# Connectors.net
KiCad netlist of a schematic drawn in Altium Designer
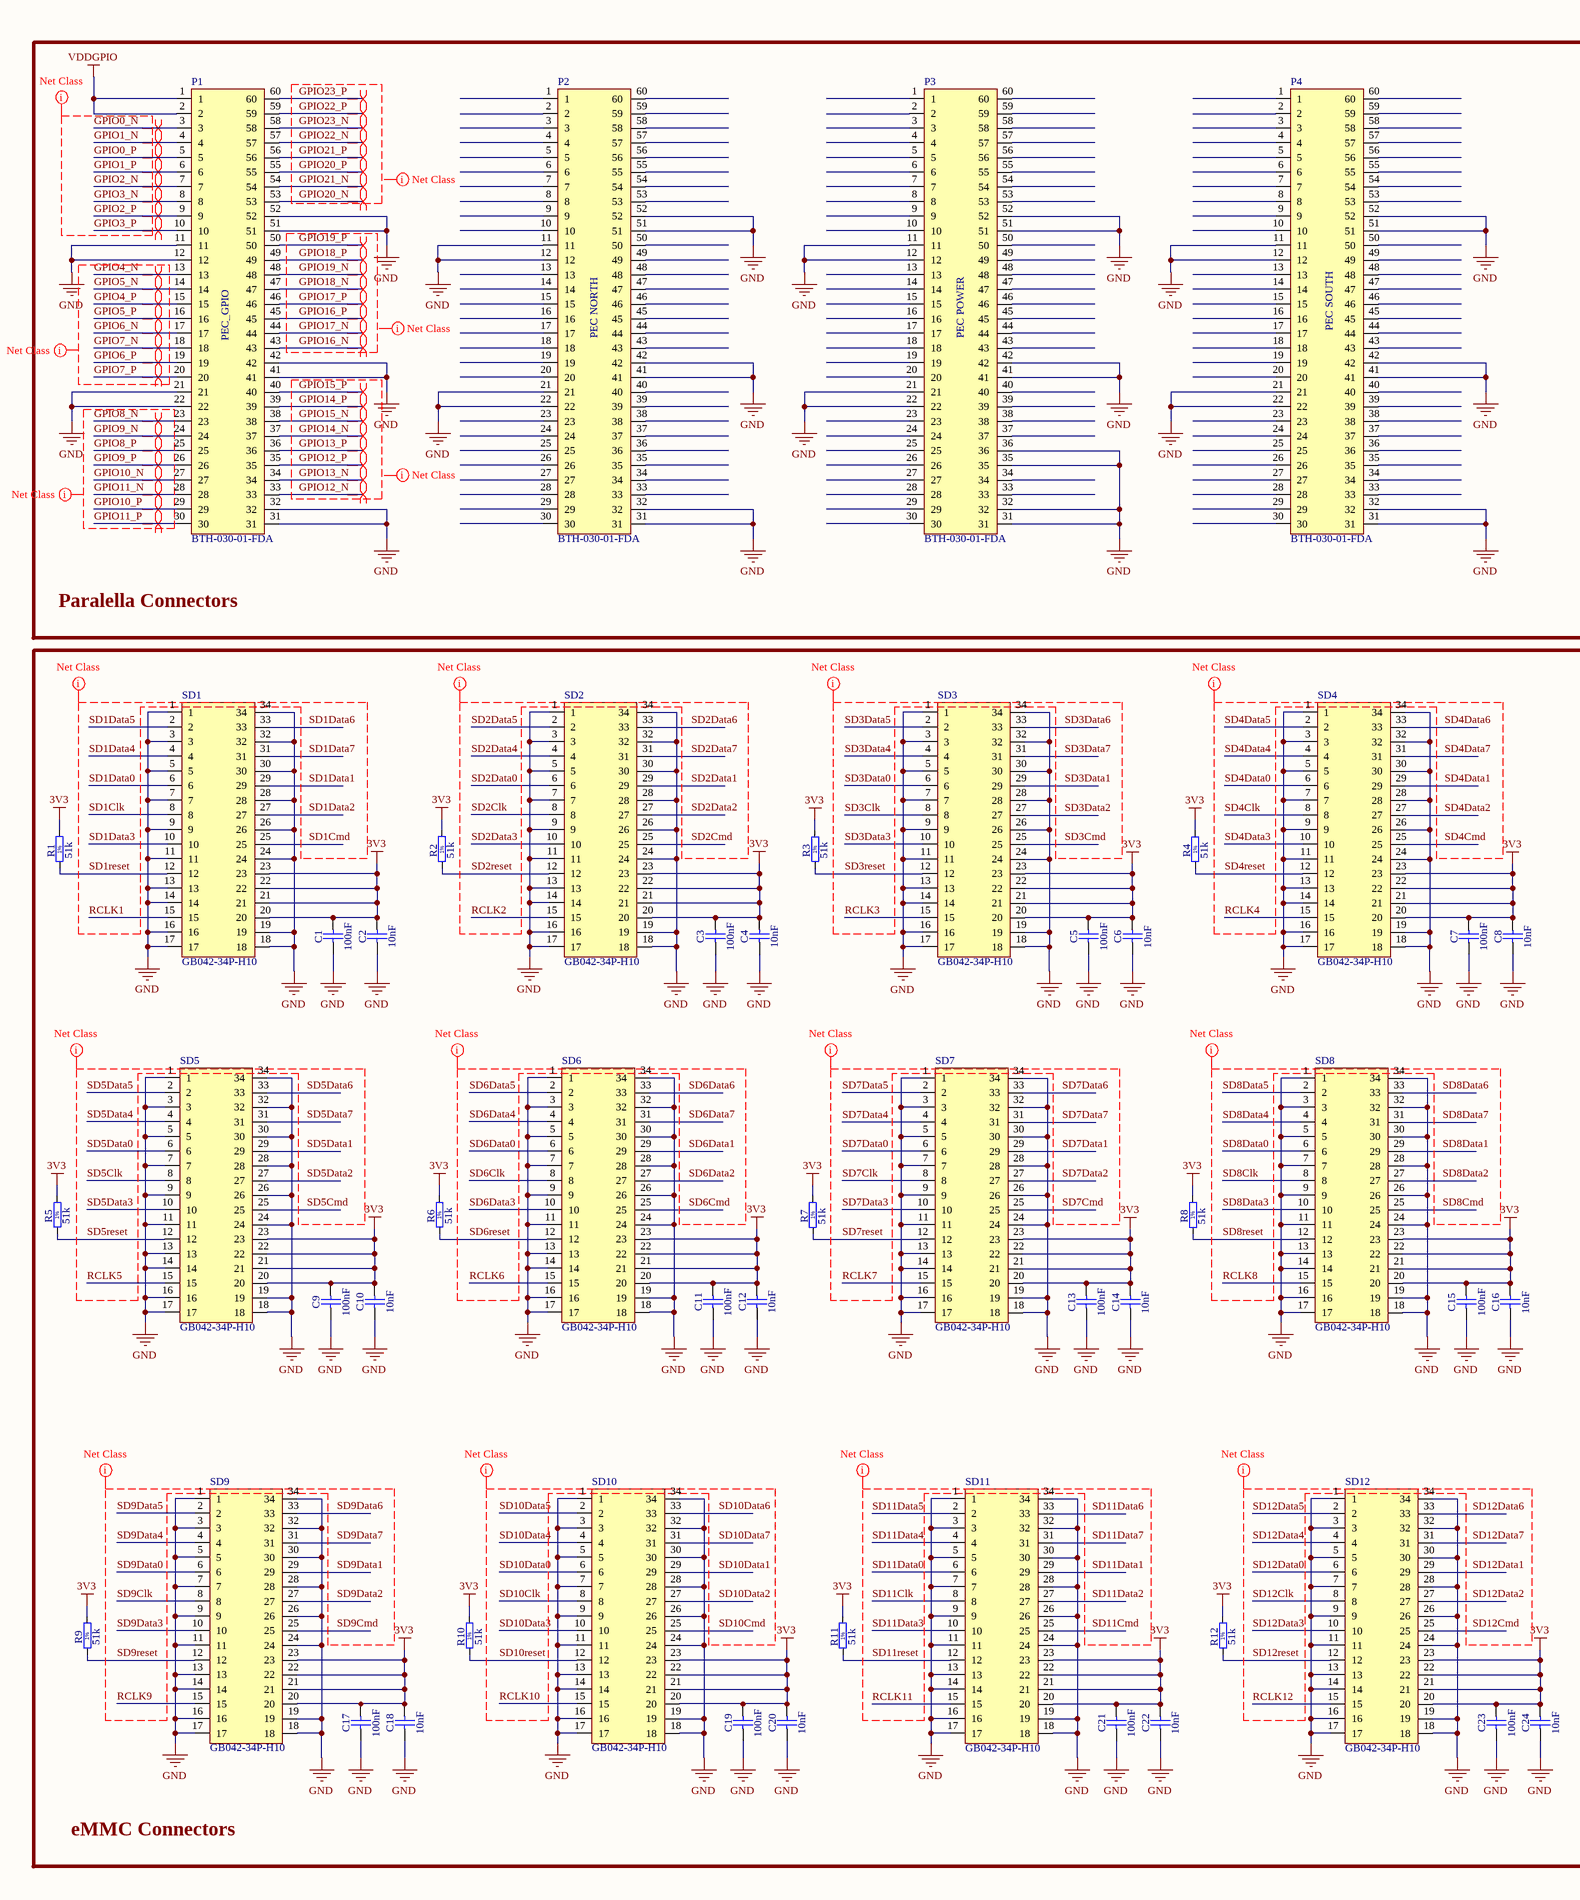
[diagram p0: Connectors.SchDoc, left]
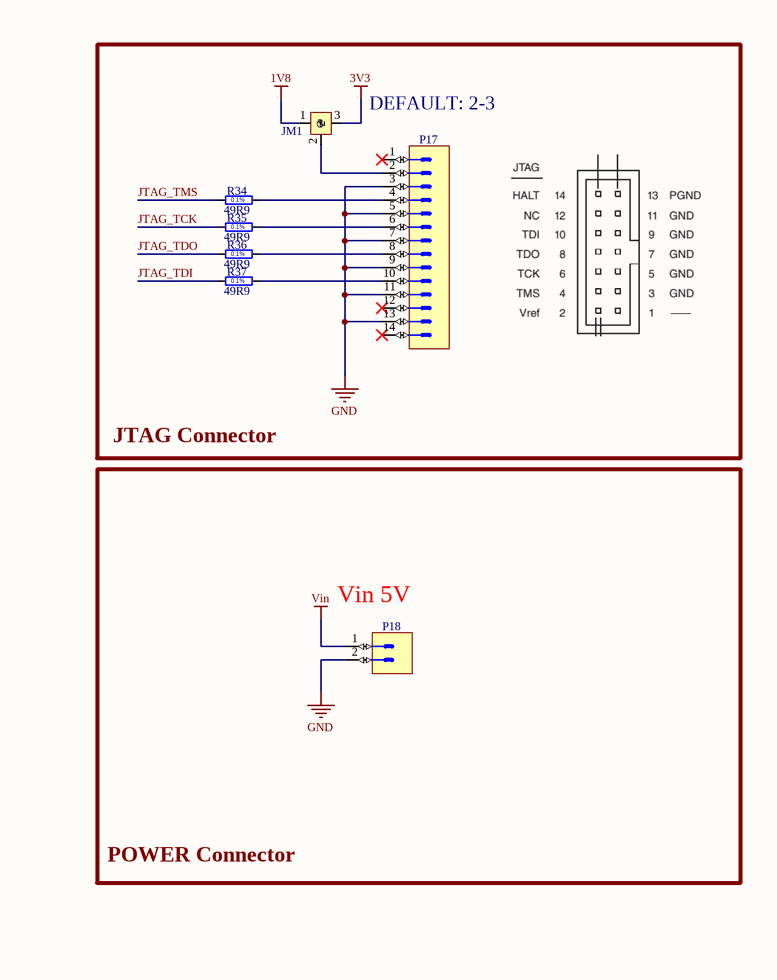
[diagram p1: Connectors.SchDoc, right]

(export (version "E")
  (design (tool "Eeschema 10.0.6"))
  (components
    (comp (ref "C1")
      (value "100nF")
      (footprint "CAPC1608X87N")
      (description "Non-polarised capacitor")
      (fields
        (field (name "PART NUMBER") "CC0603_100NF_50V_10%_X7R")
        (field (name "VOLTAGE") "50V")
        (field (name "AUTHOR") "CERN DEM JLC")
      )
      (libsource (lib "Capacitors") (part "Capacitor - non polarized"))
    )
    (comp (ref "C2")
      (value "10nF")
      (footprint "CAPC1608X87N")
      (description "Non-polarised capacitor")
      (fields
        (field (name "PART NUMBER") "CC0603_10NF_50V_10%_X7R")
        (field (name "VOLTAGE") "50V")
        (field (name "AUTHOR") "CERN DEM JLC")
      )
      (libsource (lib "Capacitors") (part "Capacitor - non polarized"))
    )
    (comp (ref "C3")
      (value "100nF")
      (footprint "CAPC1608X87N")
      (description "Non-polarised capacitor")
      (fields
        (field (name "PART NUMBER") "CC0603_100NF_50V_10%_X7R")
        (field (name "VOLTAGE") "50V")
        (field (name "AUTHOR") "CERN DEM JLC")
      )
      (libsource (lib "Capacitors") (part "Capacitor - non polarized"))
    )
    (comp (ref "C4")
      (value "10nF")
      (footprint "CAPC1608X87N")
      (description "Non-polarised capacitor")
      (fields
        (field (name "PART NUMBER") "CC0603_10NF_50V_10%_X7R")
        (field (name "VOLTAGE") "50V")
        (field (name "AUTHOR") "CERN DEM JLC")
      )
      (libsource (lib "Capacitors") (part "Capacitor - non polarized"))
    )
    (comp (ref "C5")
      (value "100nF")
      (footprint "CAPC1608X87N")
      (description "Non-polarised capacitor")
      (fields
        (field (name "PART NUMBER") "CC0603_100NF_50V_10%_X7R")
        (field (name "VOLTAGE") "50V")
        (field (name "AUTHOR") "CERN DEM JLC")
      )
      (libsource (lib "Capacitors") (part "Capacitor - non polarized"))
    )
    (comp (ref "C6")
      (value "10nF")
      (footprint "CAPC1608X87N")
      (description "Non-polarised capacitor")
      (fields
        (field (name "PART NUMBER") "CC0603_10NF_50V_10%_X7R")
        (field (name "VOLTAGE") "50V")
        (field (name "AUTHOR") "CERN DEM JLC")
      )
      (libsource (lib "Capacitors") (part "Capacitor - non polarized"))
    )
    (comp (ref "C7")
      (value "100nF")
      (footprint "CAPC1608X87N")
      (description "Non-polarised capacitor")
      (fields
        (field (name "PART NUMBER") "CC0603_100NF_50V_10%_X7R")
        (field (name "VOLTAGE") "50V")
        (field (name "AUTHOR") "CERN DEM JLC")
      )
      (libsource (lib "Capacitors") (part "Capacitor - non polarized"))
    )
    (comp (ref "C8")
      (value "10nF")
      (footprint "CAPC1608X87N")
      (description "Non-polarised capacitor")
      (fields
        (field (name "PART NUMBER") "CC0603_10NF_50V_10%_X7R")
        (field (name "VOLTAGE") "50V")
        (field (name "AUTHOR") "CERN DEM JLC")
      )
      (libsource (lib "Capacitors") (part "Capacitor - non polarized"))
    )
    (comp (ref "C9")
      (value "100nF")
      (footprint "CAPC1608X87N")
      (description "Non-polarised capacitor")
      (fields
        (field (name "PART NUMBER") "CC0603_100NF_50V_10%_X7R")
        (field (name "VOLTAGE") "50V")
        (field (name "AUTHOR") "CERN DEM JLC")
      )
      (libsource (lib "Capacitors") (part "Capacitor - non polarized"))
    )
    (comp (ref "C10")
      (value "10nF")
      (footprint "CAPC1608X87N")
      (description "Non-polarised capacitor")
      (fields
        (field (name "PART NUMBER") "CC0603_10NF_50V_10%_X7R")
        (field (name "VOLTAGE") "50V")
        (field (name "AUTHOR") "CERN DEM JLC")
      )
      (libsource (lib "Capacitors") (part "Capacitor - non polarized"))
    )
    (comp (ref "C11")
      (value "100nF")
      (footprint "CAPC1608X87N")
      (description "Non-polarised capacitor")
      (fields
        (field (name "PART NUMBER") "CC0603_100NF_50V_10%_X7R")
        (field (name "VOLTAGE") "50V")
        (field (name "AUTHOR") "CERN DEM JLC")
      )
      (libsource (lib "Capacitors") (part "Capacitor - non polarized"))
    )
    (comp (ref "C12")
      (value "10nF")
      (footprint "CAPC1608X87N")
      (description "Non-polarised capacitor")
      (fields
        (field (name "PART NUMBER") "CC0603_10NF_50V_10%_X7R")
        (field (name "VOLTAGE") "50V")
        (field (name "AUTHOR") "CERN DEM JLC")
      )
      (libsource (lib "Capacitors") (part "Capacitor - non polarized"))
    )
    (comp (ref "C13")
      (value "100nF")
      (footprint "CAPC1608X87N")
      (description "Non-polarised capacitor")
      (fields
        (field (name "PART NUMBER") "CC0603_100NF_50V_10%_X7R")
        (field (name "VOLTAGE") "50V")
        (field (name "AUTHOR") "CERN DEM JLC")
      )
      (libsource (lib "Capacitors") (part "Capacitor - non polarized"))
    )
    (comp (ref "C14")
      (value "10nF")
      (footprint "CAPC1608X87N")
      (description "Non-polarised capacitor")
      (fields
        (field (name "PART NUMBER") "CC0603_10NF_50V_10%_X7R")
        (field (name "VOLTAGE") "50V")
        (field (name "AUTHOR") "CERN DEM JLC")
      )
      (libsource (lib "Capacitors") (part "Capacitor - non polarized"))
    )
    (comp (ref "C15")
      (value "100nF")
      (footprint "CAPC1608X87N")
      (description "Non-polarised capacitor")
      (fields
        (field (name "PART NUMBER") "CC0603_100NF_50V_10%_X7R")
        (field (name "VOLTAGE") "50V")
        (field (name "AUTHOR") "CERN DEM JLC")
      )
      (libsource (lib "Capacitors") (part "Capacitor - non polarized"))
    )
    (comp (ref "C16")
      (value "10nF")
      (footprint "CAPC1608X87N")
      (description "Non-polarised capacitor")
      (fields
        (field (name "PART NUMBER") "CC0603_10NF_50V_10%_X7R")
        (field (name "VOLTAGE") "50V")
        (field (name "AUTHOR") "CERN DEM JLC")
      )
      (libsource (lib "Capacitors") (part "Capacitor - non polarized"))
    )
    (comp (ref "C17")
      (value "100nF")
      (footprint "CAPC1608X87N")
      (description "Non-polarised capacitor")
      (fields
        (field (name "PART NUMBER") "CC0603_100NF_50V_10%_X7R")
        (field (name "VOLTAGE") "50V")
        (field (name "AUTHOR") "CERN DEM JLC")
      )
      (libsource (lib "Capacitors") (part "Capacitor - non polarized"))
    )
    (comp (ref "C18")
      (value "10nF")
      (footprint "CAPC1608X87N")
      (description "Non-polarised capacitor")
      (fields
        (field (name "PART NUMBER") "CC0603_10NF_50V_10%_X7R")
        (field (name "VOLTAGE") "50V")
        (field (name "AUTHOR") "CERN DEM JLC")
      )
      (libsource (lib "Capacitors") (part "Capacitor - non polarized"))
    )
    (comp (ref "C19")
      (value "100nF")
      (footprint "CAPC1608X87N")
      (description "Non-polarised capacitor")
      (fields
        (field (name "PART NUMBER") "CC0603_100NF_50V_10%_X7R")
        (field (name "VOLTAGE") "50V")
        (field (name "AUTHOR") "CERN DEM JLC")
      )
      (libsource (lib "Capacitors") (part "Capacitor - non polarized"))
    )
    (comp (ref "C20")
      (value "10nF")
      (footprint "CAPC1608X87N")
      (description "Non-polarised capacitor")
      (fields
        (field (name "PART NUMBER") "CC0603_10NF_50V_10%_X7R")
        (field (name "VOLTAGE") "50V")
        (field (name "AUTHOR") "CERN DEM JLC")
      )
      (libsource (lib "Capacitors") (part "Capacitor - non polarized"))
    )
    (comp (ref "C21")
      (value "100nF")
      (footprint "CAPC1608X87N")
      (description "Non-polarised capacitor")
      (fields
        (field (name "PART NUMBER") "CC0603_100NF_50V_10%_X7R")
        (field (name "VOLTAGE") "50V")
        (field (name "AUTHOR") "CERN DEM JLC")
      )
      (libsource (lib "Capacitors") (part "Capacitor - non polarized"))
    )
    (comp (ref "C22")
      (value "10nF")
      (footprint "CAPC1608X87N")
      (description "Non-polarised capacitor")
      (fields
        (field (name "PART NUMBER") "CC0603_10NF_50V_10%_X7R")
        (field (name "VOLTAGE") "50V")
        (field (name "AUTHOR") "CERN DEM JLC")
      )
      (libsource (lib "Capacitors") (part "Capacitor - non polarized"))
    )
    (comp (ref "C23")
      (value "100nF")
      (footprint "CAPC1608X87N")
      (description "Non-polarised capacitor")
      (fields
        (field (name "PART NUMBER") "CC0603_100NF_50V_10%_X7R")
        (field (name "VOLTAGE") "50V")
        (field (name "AUTHOR") "CERN DEM JLC")
      )
      (libsource (lib "Capacitors") (part "Capacitor - non polarized"))
    )
    (comp (ref "C24")
      (value "10nF")
      (footprint "CAPC1608X87N")
      (description "Non-polarised capacitor")
      (fields
        (field (name "PART NUMBER") "CC0603_10NF_50V_10%_X7R")
        (field (name "VOLTAGE") "50V")
        (field (name "AUTHOR") "CERN DEM JLC")
      )
      (libsource (lib "Capacitors") (part "Capacitor - non polarized"))
    )
    (comp (ref "JM1")
      (value "Jumper 0R")
      (footprint "JUMPER_0R")
      (libsource (lib "SCHLIB") (part "Jumper 0R"))
    )
    (comp (ref "P1")
      (value "BTH-030-01-FDA")
      (footprint "BTH-030-01-F-D-A")
      (description "Connector Parallela")
      (libsource (lib "SCHLIB") (part "BTH-030-01-FDA"))
    )
    (comp (ref "P2")
      (value "BTH-030-01-FDA")
      (footprint "BTH-030-01-F-D-A")
      (description "Connector Parallela")
      (libsource (lib "SCHLIB") (part "BTH-030-01-FDA"))
    )
    (comp (ref "P3")
      (value "BTH-030-01-FDA")
      (footprint "BTH-030-01-F-D-A")
      (description "Connector Parallela")
      (libsource (lib "SCHLIB") (part "BTH-030-01-FDA"))
    )
    (comp (ref "P4")
      (value "BTH-030-01-FDA")
      (footprint "BTH-030-01-F-D-A")
      (description "Connector Parallela")
      (libsource (lib "SCHLIB") (part "BTH-030-01-FDA"))
    )
    (comp (ref "P17")
      (value "~")
      (description "Connector 14 Male")
      (fields
        (field (name "MANUFACTURER PART NUMBER") "0878321420")
        (field (name "MANUFACTURER") "Molex, LLC")
      )
      (libsource (lib "Connectors") (part "Connector 14 Male"))
    )
    (comp (ref "P18")
      (value "KK®")
      (footprint "MOLEX_26-60-4020")
      (description "Connector 2 Male")
      (fields
        (field (name "PART NUMBER") "MOLEX_26-60-4020")
        (field (name "MANUFACTURER") "Molex, LLC")
        (field (name "AUTHOR") "CERN DEM JLC")
      )
      (libsource (lib "Connectors") (part "Connector 2 Male"))
    )
    (comp (ref "R1")
      (value "51k")
      (footprint "RESC1608X55N")
      (description "Resistor - 1%")
      (fields
        (field (name "PART NUMBER") "R0603_51K_1%_0.1W_100PPM")
        (field (name "POWER") "0.1W")
        (field (name "AUTHOR") "CERN DEM JLC")
      )
      (libsource (lib "Resistors") (part "Resistor - 1%"))
    )
    (comp (ref "R2")
      (value "51k")
      (footprint "RESC1608X55N")
      (description "Resistor - 1%")
      (fields
        (field (name "PART NUMBER") "R0603_51K_1%_0.1W_100PPM")
        (field (name "POWER") "0.1W")
        (field (name "AUTHOR") "CERN DEM JLC")
      )
      (libsource (lib "Resistors") (part "Resistor - 1%"))
    )
    (comp (ref "R3")
      (value "51k")
      (footprint "RESC1608X55N")
      (description "Resistor - 1%")
      (fields
        (field (name "PART NUMBER") "R0603_51K_1%_0.1W_100PPM")
        (field (name "POWER") "0.1W")
        (field (name "AUTHOR") "CERN DEM JLC")
      )
      (libsource (lib "Resistors") (part "Resistor - 1%"))
    )
    (comp (ref "R4")
      (value "51k")
      (footprint "RESC1608X55N")
      (description "Resistor - 1%")
      (fields
        (field (name "PART NUMBER") "R0603_51K_1%_0.1W_100PPM")
        (field (name "POWER") "0.1W")
        (field (name "AUTHOR") "CERN DEM JLC")
      )
      (libsource (lib "Resistors") (part "Resistor - 1%"))
    )
    (comp (ref "R5")
      (value "51k")
      (footprint "RESC1608X55N")
      (description "Resistor - 1%")
      (fields
        (field (name "PART NUMBER") "R0603_51K_1%_0.1W_100PPM")
        (field (name "POWER") "0.1W")
        (field (name "AUTHOR") "CERN DEM JLC")
      )
      (libsource (lib "Resistors") (part "Resistor - 1%"))
    )
    (comp (ref "R6")
      (value "51k")
      (footprint "RESC1608X55N")
      (description "Resistor - 1%")
      (fields
        (field (name "PART NUMBER") "R0603_51K_1%_0.1W_100PPM")
        (field (name "POWER") "0.1W")
        (field (name "AUTHOR") "CERN DEM JLC")
      )
      (libsource (lib "Resistors") (part "Resistor - 1%"))
    )
    (comp (ref "R7")
      (value "51k")
      (footprint "RESC1608X55N")
      (description "Resistor - 1%")
      (fields
        (field (name "PART NUMBER") "R0603_51K_1%_0.1W_100PPM")
        (field (name "POWER") "0.1W")
        (field (name "AUTHOR") "CERN DEM JLC")
      )
      (libsource (lib "Resistors") (part "Resistor - 1%"))
    )
    (comp (ref "R8")
      (value "51k")
      (footprint "RESC1608X55N")
      (description "Resistor - 1%")
      (fields
        (field (name "PART NUMBER") "R0603_51K_1%_0.1W_100PPM")
        (field (name "POWER") "0.1W")
        (field (name "AUTHOR") "CERN DEM JLC")
      )
      (libsource (lib "Resistors") (part "Resistor - 1%"))
    )
    (comp (ref "R9")
      (value "51k")
      (footprint "RESC1608X55N")
      (description "Resistor - 1%")
      (fields
        (field (name "PART NUMBER") "R0603_51K_1%_0.1W_100PPM")
        (field (name "POWER") "0.1W")
        (field (name "AUTHOR") "CERN DEM JLC")
      )
      (libsource (lib "Resistors") (part "Resistor - 1%"))
    )
    (comp (ref "R10")
      (value "51k")
      (footprint "RESC1608X55N")
      (description "Resistor - 1%")
      (fields
        (field (name "PART NUMBER") "R0603_51K_1%_0.1W_100PPM")
        (field (name "POWER") "0.1W")
        (field (name "AUTHOR") "CERN DEM JLC")
      )
      (libsource (lib "Resistors") (part "Resistor - 1%"))
    )
    (comp (ref "R11")
      (value "51k")
      (footprint "RESC1608X55N")
      (description "Resistor - 1%")
      (fields
        (field (name "PART NUMBER") "R0603_51K_1%_0.1W_100PPM")
        (field (name "POWER") "0.1W")
        (field (name "AUTHOR") "CERN DEM JLC")
      )
      (libsource (lib "Resistors") (part "Resistor - 1%"))
    )
    (comp (ref "R12")
      (value "51k")
      (footprint "RESC1608X55N")
      (description "Resistor - 1%")
      (fields
        (field (name "PART NUMBER") "R0603_51K_1%_0.1W_100PPM")
        (field (name "POWER") "0.1W")
        (field (name "AUTHOR") "CERN DEM JLC")
      )
      (libsource (lib "Resistors") (part "Resistor - 1%"))
    )
    (comp (ref "R34")
      (value "49R9")
      (footprint "RESC1608X55N")
      (description "Resistor - 0.1%")
      (fields
        (field (name "PART NUMBER") "R0603_49R9_0.1%_0.063W_10PPM")
        (field (name "POWER") "0.063W")
        (field (name "AUTHOR") "CERN DEM JLC")
      )
      (libsource (lib "Resistors") (part "Resistor - 0.1%"))
    )
    (comp (ref "R35")
      (value "49R9")
      (footprint "RESC1608X55N")
      (description "Resistor - 0.1%")
      (fields
        (field (name "PART NUMBER") "R0603_49R9_0.1%_0.063W_10PPM")
        (field (name "POWER") "0.063W")
        (field (name "AUTHOR") "CERN DEM JLC")
      )
      (libsource (lib "Resistors") (part "Resistor - 0.1%"))
    )
    (comp (ref "R36")
      (value "49R9")
      (footprint "RESC1608X55N")
      (description "Resistor - 0.1%")
      (fields
        (field (name "PART NUMBER") "R0603_49R9_0.1%_0.063W_10PPM")
        (field (name "POWER") "0.063W")
        (field (name "AUTHOR") "CERN DEM JLC")
      )
      (libsource (lib "Resistors") (part "Resistor - 0.1%"))
    )
    (comp (ref "R37")
      (value "49R9")
      (footprint "RESC1608X55N")
      (description "Resistor - 0.1%")
      (fields
        (field (name "PART NUMBER") "R0603_49R9_0.1%_0.063W_10PPM")
        (field (name "POWER") "0.063W")
        (field (name "AUTHOR") "CERN DEM JLC")
      )
      (libsource (lib "Resistors") (part "Resistor - 0.1%"))
    )
    (comp (ref "SD1")
      (value "GB042-34P-H10")
      (footprint "GB042-34P-H10")
      (description "Connector, eMMC")
      (libsource (lib "SCHLIB") (part "GB042-34P-H10"))
    )
    (comp (ref "SD2")
      (value "GB042-34P-H10")
      (footprint "GB042-34P-H10")
      (description "Connector, eMMC")
      (libsource (lib "SCHLIB") (part "GB042-34P-H10"))
    )
    (comp (ref "SD3")
      (value "GB042-34P-H10")
      (footprint "GB042-34P-H10")
      (description "Connector, eMMC")
      (libsource (lib "SCHLIB") (part "GB042-34P-H10"))
    )
    (comp (ref "SD4")
      (value "GB042-34P-H10")
      (footprint "GB042-34P-H10")
      (description "Connector, eMMC")
      (libsource (lib "SCHLIB") (part "GB042-34P-H10"))
    )
    (comp (ref "SD5")
      (value "GB042-34P-H10")
      (footprint "GB042-34P-H10")
      (description "Connector, eMMC")
      (libsource (lib "SCHLIB") (part "GB042-34P-H10"))
    )
    (comp (ref "SD6")
      (value "GB042-34P-H10")
      (footprint "GB042-34P-H10")
      (description "Connector, eMMC")
      (libsource (lib "SCHLIB") (part "GB042-34P-H10"))
    )
    (comp (ref "SD7")
      (value "GB042-34P-H10")
      (footprint "GB042-34P-H10")
      (description "Connector, eMMC")
      (libsource (lib "SCHLIB") (part "GB042-34P-H10"))
    )
    (comp (ref "SD8")
      (value "GB042-34P-H10")
      (footprint "GB042-34P-H10")
      (description "Connector, eMMC")
      (libsource (lib "SCHLIB") (part "GB042-34P-H10"))
    )
    (comp (ref "SD9")
      (value "GB042-34P-H10")
      (footprint "GB042-34P-H10")
      (description "Connector, eMMC")
      (libsource (lib "SCHLIB") (part "GB042-34P-H10"))
    )
    (comp (ref "SD10")
      (value "GB042-34P-H10")
      (footprint "GB042-34P-H10")
      (description "Connector, eMMC")
      (libsource (lib "SCHLIB") (part "GB042-34P-H10"))
    )
    (comp (ref "SD11")
      (value "GB042-34P-H10")
      (footprint "GB042-34P-H10")
      (description "Connector, eMMC")
      (libsource (lib "SCHLIB") (part "GB042-34P-H10"))
    )
    (comp (ref "SD12")
      (value "GB042-34P-H10")
      (footprint "GB042-34P-H10")
      (description "Connector, eMMC")
      (libsource (lib "SCHLIB") (part "GB042-34P-H10"))
    )
  )
  (nets
    (net (code "1") (name "/GPIO0_N") (class "Default")
      (node (ref "P1") (pin "3") (pinfunction "3_3") (pintype "passive"))
    )
    (net (code "2") (name "/GPIO0_P") (class "Default")
      (node (ref "P1") (pin "5") (pinfunction "5_5") (pintype "passive"))
    )
    (net (code "3") (name "/GPIO1_N") (class "Default")
      (node (ref "P1") (pin "4") (pinfunction "4_4") (pintype "passive"))
    )
    (net (code "4") (name "/GPIO1_P") (class "Default")
      (node (ref "P1") (pin "6") (pinfunction "6_6") (pintype "passive"))
    )
    (net (code "5") (name "/GPIO2_N") (class "Default")
      (node (ref "P1") (pin "7") (pinfunction "7_7") (pintype "passive"))
    )
    (net (code "6") (name "/GPIO2_P") (class "Default")
      (node (ref "P1") (pin "9") (pinfunction "9_9") (pintype "passive"))
    )
    (net (code "7") (name "/GPIO3_N") (class "Default")
      (node (ref "P1") (pin "8") (pinfunction "8_8") (pintype "passive"))
    )
    (net (code "8") (name "/GPIO3_P") (class "Default")
      (node (ref "P1") (pin "10") (pinfunction "10_10") (pintype "passive"))
    )
    (net (code "9") (name "/GPIO4_N") (class "Default")
      (node (ref "P1") (pin "13") (pinfunction "13_13") (pintype "passive"))
    )
    (net (code "10") (name "/GPIO4_P") (class "Default")
      (node (ref "P1") (pin "15") (pinfunction "15_15") (pintype "passive"))
    )
    (net (code "11") (name "/GPIO5_N") (class "Default")
      (node (ref "P1") (pin "14") (pinfunction "14_14") (pintype "passive"))
    )
    (net (code "12") (name "/GPIO5_P") (class "Default")
      (node (ref "P1") (pin "16") (pinfunction "16_16") (pintype "passive"))
    )
    (net (code "13") (name "/GPIO6_N") (class "Default")
      (node (ref "P1") (pin "17") (pinfunction "17_17") (pintype "passive"))
    )
    (net (code "14") (name "/GPIO6_P") (class "Default")
      (node (ref "P1") (pin "19") (pinfunction "19_19") (pintype "passive"))
    )
    (net (code "15") (name "/GPIO7_N") (class "Default")
      (node (ref "P1") (pin "18") (pinfunction "18_18") (pintype "passive"))
    )
    (net (code "16") (name "/GPIO7_P") (class "Default")
      (node (ref "P1") (pin "20") (pinfunction "20_20") (pintype "passive"))
    )
    (net (code "17") (name "/GPIO8_N") (class "Default")
      (node (ref "P1") (pin "23") (pinfunction "23_23") (pintype "passive"))
    )
    (net (code "18") (name "/GPIO8_P") (class "Default")
      (node (ref "P1") (pin "25") (pinfunction "25_25") (pintype "passive"))
    )
    (net (code "19") (name "/GPIO9_N") (class "Default")
      (node (ref "P1") (pin "24") (pinfunction "24_24") (pintype "passive"))
    )
    (net (code "20") (name "/GPIO9_P") (class "Default")
      (node (ref "P1") (pin "26") (pinfunction "26_26") (pintype "passive"))
    )
    (net (code "21") (name "/GPIO10_N") (class "Default")
      (node (ref "P1") (pin "27") (pinfunction "27_27") (pintype "passive"))
    )
    (net (code "22") (name "/GPIO10_P") (class "Default")
      (node (ref "P1") (pin "29") (pinfunction "29_29") (pintype "passive"))
    )
    (net (code "23") (name "/GPIO11_N") (class "Default")
      (node (ref "P1") (pin "28") (pinfunction "28_28") (pintype "passive"))
    )
    (net (code "24") (name "/GPIO11_P") (class "Default")
      (node (ref "P1") (pin "30") (pinfunction "30_30") (pintype "passive"))
    )
    (net (code "25") (name "/GPIO12_N") (class "Default")
      (node (ref "P1") (pin "33") (pinfunction "33_33") (pintype "passive"))
    )
    (net (code "26") (name "/GPIO12_P") (class "Default")
      (node (ref "P1") (pin "35") (pinfunction "35_35") (pintype "passive"))
    )
    (net (code "27") (name "/GPIO13_N") (class "Default")
      (node (ref "P1") (pin "34") (pinfunction "34_34") (pintype "passive"))
    )
    (net (code "28") (name "/GPIO13_P") (class "Default")
      (node (ref "P1") (pin "36") (pinfunction "36_36") (pintype "passive"))
    )
    (net (code "29") (name "/GPIO14_N") (class "Default")
      (node (ref "P1") (pin "37") (pinfunction "37_37") (pintype "passive"))
    )
    (net (code "30") (name "/GPIO14_P") (class "Default")
      (node (ref "P1") (pin "39") (pinfunction "39_39") (pintype "passive"))
    )
    (net (code "31") (name "/GPIO15_N") (class "Default")
      (node (ref "P1") (pin "38") (pinfunction "38_38") (pintype "passive"))
    )
    (net (code "32") (name "/GPIO15_P") (class "Default")
      (node (ref "P1") (pin "40") (pinfunction "40_40") (pintype "passive"))
    )
    (net (code "33") (name "/GPIO16_N") (class "Default")
      (node (ref "P1") (pin "43") (pinfunction "43_43") (pintype "passive"))
    )
    (net (code "34") (name "/GPIO16_P") (class "Default")
      (node (ref "P1") (pin "45") (pinfunction "45_45") (pintype "passive"))
    )
    (net (code "35") (name "/GPIO17_N") (class "Default")
      (node (ref "P1") (pin "44") (pinfunction "44_44") (pintype "passive"))
    )
    (net (code "36") (name "/GPIO17_P") (class "Default")
      (node (ref "P1") (pin "46") (pinfunction "46_46") (pintype "passive"))
    )
    (net (code "37") (name "/GPIO18_N") (class "Default")
      (node (ref "P1") (pin "47") (pinfunction "47_47") (pintype "passive"))
    )
    (net (code "38") (name "/GPIO18_P") (class "Default")
      (node (ref "P1") (pin "49") (pinfunction "49_49") (pintype "passive"))
    )
    (net (code "39") (name "/GPIO19_N") (class "Default")
      (node (ref "P1") (pin "48") (pinfunction "48_48") (pintype "passive"))
    )
    (net (code "40") (name "/GPIO19_P") (class "Default")
      (node (ref "P1") (pin "50") (pinfunction "50_50") (pintype "passive"))
    )
    (net (code "41") (name "/GPIO20_N") (class "Default")
      (node (ref "P1") (pin "53") (pinfunction "53_53") (pintype "passive"))
    )
    (net (code "42") (name "/GPIO20_P") (class "Default")
      (node (ref "P1") (pin "55") (pinfunction "55_55") (pintype "passive"))
    )
    (net (code "43") (name "/GPIO21_N") (class "Default")
      (node (ref "P1") (pin "54") (pinfunction "54_54") (pintype "passive"))
    )
    (net (code "44") (name "/GPIO21_P") (class "Default")
      (node (ref "P1") (pin "56") (pinfunction "56_56") (pintype "passive"))
    )
    (net (code "45") (name "/GPIO22_N") (class "Default")
      (node (ref "P1") (pin "57") (pinfunction "57_57") (pintype "passive"))
    )
    (net (code "46") (name "/GPIO22_P") (class "Default")
      (node (ref "P1") (pin "59") (pinfunction "59_59") (pintype "passive"))
    )
    (net (code "47") (name "/GPIO23_N") (class "Default")
      (node (ref "P1") (pin "58") (pinfunction "58_58") (pintype "passive"))
    )
    (net (code "48") (name "/GPIO23_P") (class "Default")
      (node (ref "P1") (pin "60") (pinfunction "60_60") (pintype "passive"))
    )
    (net (code "49") (name "/JTAG_TCK") (class "Default")
      (node (ref "R35") (pin "1") (pinfunction "1_1") (pintype "passive"))
    )
    (net (code "50") (name "/JTAG_TDI") (class "Default")
      (node (ref "R37") (pin "1") (pinfunction "1_1") (pintype "passive"))
    )
    (net (code "51") (name "/JTAG_TDO") (class "Default")
      (node (ref "R36") (pin "1") (pinfunction "1_1") (pintype "passive"))
    )
    (net (code "52") (name "/JTAG_TMS") (class "Default")
      (node (ref "R34") (pin "1") (pinfunction "1_1") (pintype "passive"))
    )
    (net (code "53") (name "/RCLK1") (class "Default")
      (node (ref "SD1") (pin "15") (pinfunction "15_15") (pintype "passive"))
    )
    (net (code "54") (name "/RCLK2") (class "Default")
      (node (ref "SD2") (pin "15") (pinfunction "15_15") (pintype "passive"))
    )
    (net (code "55") (name "/RCLK3") (class "Default")
      (node (ref "SD3") (pin "15") (pinfunction "15_15") (pintype "passive"))
    )
    (net (code "56") (name "/RCLK4") (class "Default")
      (node (ref "SD4") (pin "15") (pinfunction "15_15") (pintype "passive"))
    )
    (net (code "57") (name "/RCLK5") (class "Default")
      (node (ref "SD5") (pin "15") (pinfunction "15_15") (pintype "passive"))
    )
    (net (code "58") (name "/RCLK6") (class "Default")
      (node (ref "SD6") (pin "15") (pinfunction "15_15") (pintype "passive"))
    )
    (net (code "59") (name "/RCLK7") (class "Default")
      (node (ref "SD7") (pin "15") (pinfunction "15_15") (pintype "passive"))
    )
    (net (code "60") (name "/RCLK8") (class "Default")
      (node (ref "SD8") (pin "15") (pinfunction "15_15") (pintype "passive"))
    )
    (net (code "61") (name "/RCLK9") (class "Default")
      (node (ref "SD9") (pin "15") (pinfunction "15_15") (pintype "passive"))
    )
    (net (code "62") (name "/RCLK10") (class "Default")
      (node (ref "SD10") (pin "15") (pinfunction "15_15") (pintype "passive"))
    )
    (net (code "63") (name "/RCLK11") (class "Default")
      (node (ref "SD11") (pin "15") (pinfunction "15_15") (pintype "passive"))
    )
    (net (code "64") (name "/RCLK12") (class "Default")
      (node (ref "SD12") (pin "15") (pinfunction "15_15") (pintype "passive"))
    )
    (net (code "65") (name "/SD1Clk") (class "Default")
      (node (ref "SD1") (pin "8") (pinfunction "8_8") (pintype "passive"))
    )
    (net (code "66") (name "/SD1Cmd") (class "Default")
      (node (ref "SD1") (pin "25") (pinfunction "25_25") (pintype "passive"))
    )
    (net (code "67") (name "/SD1Data0") (class "Default")
      (node (ref "SD1") (pin "6") (pinfunction "6_6") (pintype "passive"))
    )
    (net (code "68") (name "/SD1Data1") (class "Default")
      (node (ref "SD1") (pin "29") (pinfunction "29_29") (pintype "passive"))
    )
    (net (code "69") (name "/SD1Data2") (class "Default")
      (node (ref "SD1") (pin "27") (pinfunction "27_27") (pintype "passive"))
    )
    (net (code "70") (name "/SD1Data3") (class "Default")
      (node (ref "SD1") (pin "10") (pinfunction "10_10") (pintype "passive"))
    )
    (net (code "71") (name "/SD1Data4") (class "Default")
      (node (ref "SD1") (pin "4") (pinfunction "4_4") (pintype "passive"))
    )
    (net (code "72") (name "/SD1Data5") (class "Default")
      (node (ref "SD1") (pin "2") (pinfunction "2_2") (pintype "passive"))
    )
    (net (code "73") (name "/SD1Data6") (class "Default")
      (node (ref "SD1") (pin "33") (pinfunction "33_33") (pintype "passive"))
    )
    (net (code "74") (name "/SD1Data7") (class "Default")
      (node (ref "SD1") (pin "31") (pinfunction "31_31") (pintype "passive"))
    )
    (net (code "75") (name "/SD1reset") (class "Default")
      (node (ref "R1") (pin "1") (pinfunction "1_1") (pintype "passive"))
      (node (ref "SD1") (pin "12") (pinfunction "12_12") (pintype "passive"))
    )
    (net (code "76") (name "/SD2Clk") (class "Default")
      (node (ref "SD2") (pin "8") (pinfunction "8_8") (pintype "passive"))
    )
    (net (code "77") (name "/SD2Cmd") (class "Default")
      (node (ref "SD2") (pin "25") (pinfunction "25_25") (pintype "passive"))
    )
    (net (code "78") (name "/SD2Data0") (class "Default")
      (node (ref "SD2") (pin "6") (pinfunction "6_6") (pintype "passive"))
    )
    (net (code "79") (name "/SD2Data1") (class "Default")
      (node (ref "SD2") (pin "29") (pinfunction "29_29") (pintype "passive"))
    )
    (net (code "80") (name "/SD2Data2") (class "Default")
      (node (ref "SD2") (pin "27") (pinfunction "27_27") (pintype "passive"))
    )
    (net (code "81") (name "/SD2Data3") (class "Default")
      (node (ref "SD2") (pin "10") (pinfunction "10_10") (pintype "passive"))
    )
    (net (code "82") (name "/SD2Data4") (class "Default")
      (node (ref "SD2") (pin "4") (pinfunction "4_4") (pintype "passive"))
    )
    (net (code "83") (name "/SD2Data5") (class "Default")
      (node (ref "SD2") (pin "2") (pinfunction "2_2") (pintype "passive"))
    )
    (net (code "84") (name "/SD2Data6") (class "Default")
      (node (ref "SD2") (pin "33") (pinfunction "33_33") (pintype "passive"))
    )
    (net (code "85") (name "/SD2Data7") (class "Default")
      (node (ref "SD2") (pin "31") (pinfunction "31_31") (pintype "passive"))
    )
    (net (code "86") (name "/SD2reset") (class "Default")
      (node (ref "R2") (pin "1") (pinfunction "1_1") (pintype "passive"))
      (node (ref "SD2") (pin "12") (pinfunction "12_12") (pintype "passive"))
    )
    (net (code "87") (name "/SD3Clk") (class "Default")
      (node (ref "SD3") (pin "8") (pinfunction "8_8") (pintype "passive"))
    )
    (net (code "88") (name "/SD3Cmd") (class "Default")
      (node (ref "SD3") (pin "25") (pinfunction "25_25") (pintype "passive"))
    )
    (net (code "89") (name "/SD3Data0") (class "Default")
      (node (ref "SD3") (pin "6") (pinfunction "6_6") (pintype "passive"))
    )
    (net (code "90") (name "/SD3Data1") (class "Default")
      (node (ref "SD3") (pin "29") (pinfunction "29_29") (pintype "passive"))
    )
    (net (code "91") (name "/SD3Data2") (class "Default")
      (node (ref "SD3") (pin "27") (pinfunction "27_27") (pintype "passive"))
    )
    (net (code "92") (name "/SD3Data3") (class "Default")
      (node (ref "SD3") (pin "10") (pinfunction "10_10") (pintype "passive"))
    )
    (net (code "93") (name "/SD3Data4") (class "Default")
      (node (ref "SD3") (pin "4") (pinfunction "4_4") (pintype "passive"))
    )
    (net (code "94") (name "/SD3Data5") (class "Default")
      (node (ref "SD3") (pin "2") (pinfunction "2_2") (pintype "passive"))
    )
    (net (code "95") (name "/SD3Data6") (class "Default")
      (node (ref "SD3") (pin "33") (pinfunction "33_33") (pintype "passive"))
    )
    (net (code "96") (name "/SD3Data7") (class "Default")
      (node (ref "SD3") (pin "31") (pinfunction "31_31") (pintype "passive"))
    )
    (net (code "97") (name "/SD3reset") (class "Default")
      (node (ref "R3") (pin "1") (pinfunction "1_1") (pintype "passive"))
      (node (ref "SD3") (pin "12") (pinfunction "12_12") (pintype "passive"))
    )
    (net (code "98") (name "/SD4Clk") (class "Default")
      (node (ref "SD4") (pin "8") (pinfunction "8_8") (pintype "passive"))
    )
    (net (code "99") (name "/SD4Cmd") (class "Default")
      (node (ref "SD4") (pin "25") (pinfunction "25_25") (pintype "passive"))
    )
    (net (code "100") (name "/SD4Data0") (class "Default")
      (node (ref "SD4") (pin "6") (pinfunction "6_6") (pintype "passive"))
    )
    (net (code "101") (name "/SD4Data1") (class "Default")
      (node (ref "SD4") (pin "29") (pinfunction "29_29") (pintype "passive"))
    )
    (net (code "102") (name "/SD4Data2") (class "Default")
      (node (ref "SD4") (pin "27") (pinfunction "27_27") (pintype "passive"))
    )
    (net (code "103") (name "/SD4Data3") (class "Default")
      (node (ref "SD4") (pin "10") (pinfunction "10_10") (pintype "passive"))
    )
    (net (code "104") (name "/SD4Data4") (class "Default")
      (node (ref "SD4") (pin "4") (pinfunction "4_4") (pintype "passive"))
    )
    (net (code "105") (name "/SD4Data5") (class "Default")
      (node (ref "SD4") (pin "2") (pinfunction "2_2") (pintype "passive"))
    )
    (net (code "106") (name "/SD4Data6") (class "Default")
      (node (ref "SD4") (pin "33") (pinfunction "33_33") (pintype "passive"))
    )
    (net (code "107") (name "/SD4Data7") (class "Default")
      (node (ref "SD4") (pin "31") (pinfunction "31_31") (pintype "passive"))
    )
    (net (code "108") (name "/SD4reset") (class "Default")
      (node (ref "R4") (pin "1") (pinfunction "1_1") (pintype "passive"))
      (node (ref "SD4") (pin "12") (pinfunction "12_12") (pintype "passive"))
    )
    (net (code "109") (name "/SD5Clk") (class "Default")
      (node (ref "SD5") (pin "8") (pinfunction "8_8") (pintype "passive"))
    )
    (net (code "110") (name "/SD5Cmd") (class "Default")
      (node (ref "SD5") (pin "25") (pinfunction "25_25") (pintype "passive"))
    )
    (net (code "111") (name "/SD5Data0") (class "Default")
      (node (ref "SD5") (pin "6") (pinfunction "6_6") (pintype "passive"))
    )
    (net (code "112") (name "/SD5Data1") (class "Default")
      (node (ref "SD5") (pin "29") (pinfunction "29_29") (pintype "passive"))
    )
    (net (code "113") (name "/SD5Data2") (class "Default")
      (node (ref "SD5") (pin "27") (pinfunction "27_27") (pintype "passive"))
    )
    (net (code "114") (name "/SD5Data3") (class "Default")
      (node (ref "SD5") (pin "10") (pinfunction "10_10") (pintype "passive"))
    )
    (net (code "115") (name "/SD5Data4") (class "Default")
      (node (ref "SD5") (pin "4") (pinfunction "4_4") (pintype "passive"))
    )
    (net (code "116") (name "/SD5Data5") (class "Default")
      (node (ref "SD5") (pin "2") (pinfunction "2_2") (pintype "passive"))
    )
    (net (code "117") (name "/SD5Data6") (class "Default")
      (node (ref "SD5") (pin "33") (pinfunction "33_33") (pintype "passive"))
    )
    (net (code "118") (name "/SD5Data7") (class "Default")
      (node (ref "SD5") (pin "31") (pinfunction "31_31") (pintype "passive"))
    )
    (net (code "119") (name "/SD5reset") (class "Default")
      (node (ref "R5") (pin "1") (pinfunction "1_1") (pintype "passive"))
      (node (ref "SD5") (pin "12") (pinfunction "12_12") (pintype "passive"))
    )
    (net (code "120") (name "/SD6Clk") (class "Default")
      (node (ref "SD6") (pin "8") (pinfunction "8_8") (pintype "passive"))
    )
    (net (code "121") (name "/SD6Cmd") (class "Default")
      (node (ref "SD6") (pin "25") (pinfunction "25_25") (pintype "passive"))
    )
    (net (code "122") (name "/SD6Data0") (class "Default")
      (node (ref "SD6") (pin "6") (pinfunction "6_6") (pintype "passive"))
    )
    (net (code "123") (name "/SD6Data1") (class "Default")
      (node (ref "SD6") (pin "29") (pinfunction "29_29") (pintype "passive"))
    )
    (net (code "124") (name "/SD6Data2") (class "Default")
      (node (ref "SD6") (pin "27") (pinfunction "27_27") (pintype "passive"))
    )
    (net (code "125") (name "/SD6Data3") (class "Default")
      (node (ref "SD6") (pin "10") (pinfunction "10_10") (pintype "passive"))
    )
    (net (code "126") (name "/SD6Data4") (class "Default")
      (node (ref "SD6") (pin "4") (pinfunction "4_4") (pintype "passive"))
    )
    (net (code "127") (name "/SD6Data5") (class "Default")
      (node (ref "SD6") (pin "2") (pinfunction "2_2") (pintype "passive"))
    )
    (net (code "128") (name "/SD6Data6") (class "Default")
      (node (ref "SD6") (pin "33") (pinfunction "33_33") (pintype "passive"))
    )
    (net (code "129") (name "/SD6Data7") (class "Default")
      (node (ref "SD6") (pin "31") (pinfunction "31_31") (pintype "passive"))
    )
    (net (code "130") (name "/SD6reset") (class "Default")
      (node (ref "R6") (pin "1") (pinfunction "1_1") (pintype "passive"))
      (node (ref "SD6") (pin "12") (pinfunction "12_12") (pintype "passive"))
    )
    (net (code "131") (name "/SD7Clk") (class "Default")
      (node (ref "SD7") (pin "8") (pinfunction "8_8") (pintype "passive"))
    )
    (net (code "132") (name "/SD7Cmd") (class "Default")
      (node (ref "SD7") (pin "25") (pinfunction "25_25") (pintype "passive"))
    )
    (net (code "133") (name "/SD7Data0") (class "Default")
      (node (ref "SD7") (pin "6") (pinfunction "6_6") (pintype "passive"))
    )
    (net (code "134") (name "/SD7Data1") (class "Default")
      (node (ref "SD7") (pin "29") (pinfunction "29_29") (pintype "passive"))
    )
    (net (code "135") (name "/SD7Data2") (class "Default")
      (node (ref "SD7") (pin "27") (pinfunction "27_27") (pintype "passive"))
    )
    (net (code "136") (name "/SD7Data3") (class "Default")
      (node (ref "SD7") (pin "10") (pinfunction "10_10") (pintype "passive"))
    )
    (net (code "137") (name "/SD7Data4") (class "Default")
      (node (ref "SD7") (pin "4") (pinfunction "4_4") (pintype "passive"))
    )
    (net (code "138") (name "/SD7Data5") (class "Default")
      (node (ref "SD7") (pin "2") (pinfunction "2_2") (pintype "passive"))
    )
    (net (code "139") (name "/SD7Data6") (class "Default")
      (node (ref "SD7") (pin "33") (pinfunction "33_33") (pintype "passive"))
    )
    (net (code "140") (name "/SD7Data7") (class "Default")
      (node (ref "SD7") (pin "31") (pinfunction "31_31") (pintype "passive"))
    )
    (net (code "141") (name "/SD7reset") (class "Default")
      (node (ref "R7") (pin "1") (pinfunction "1_1") (pintype "passive"))
      (node (ref "SD7") (pin "12") (pinfunction "12_12") (pintype "passive"))
    )
    (net (code "142") (name "/SD8Clk") (class "Default")
      (node (ref "SD8") (pin "8") (pinfunction "8_8") (pintype "passive"))
    )
    (net (code "143") (name "/SD8Cmd") (class "Default")
      (node (ref "SD8") (pin "25") (pinfunction "25_25") (pintype "passive"))
    )
    (net (code "144") (name "/SD8Data0") (class "Default")
      (node (ref "SD8") (pin "6") (pinfunction "6_6") (pintype "passive"))
    )
    (net (code "145") (name "/SD8Data1") (class "Default")
      (node (ref "SD8") (pin "29") (pinfunction "29_29") (pintype "passive"))
    )
    (net (code "146") (name "/SD8Data2") (class "Default")
      (node (ref "SD8") (pin "27") (pinfunction "27_27") (pintype "passive"))
    )
    (net (code "147") (name "/SD8Data3") (class "Default")
      (node (ref "SD8") (pin "10") (pinfunction "10_10") (pintype "passive"))
    )
    (net (code "148") (name "/SD8Data4") (class "Default")
      (node (ref "SD8") (pin "4") (pinfunction "4_4") (pintype "passive"))
    )
    (net (code "149") (name "/SD8Data5") (class "Default")
      (node (ref "SD8") (pin "2") (pinfunction "2_2") (pintype "passive"))
    )
    (net (code "150") (name "/SD8Data6") (class "Default")
      (node (ref "SD8") (pin "33") (pinfunction "33_33") (pintype "passive"))
    )
    (net (code "151") (name "/SD8Data7") (class "Default")
      (node (ref "SD8") (pin "31") (pinfunction "31_31") (pintype "passive"))
    )
    (net (code "152") (name "/SD8reset") (class "Default")
      (node (ref "R8") (pin "1") (pinfunction "1_1") (pintype "passive"))
      (node (ref "SD8") (pin "12") (pinfunction "12_12") (pintype "passive"))
    )
    (net (code "153") (name "/SD9Clk") (class "Default")
      (node (ref "SD9") (pin "8") (pinfunction "8_8") (pintype "passive"))
    )
    (net (code "154") (name "/SD9Cmd") (class "Default")
      (node (ref "SD9") (pin "25") (pinfunction "25_25") (pintype "passive"))
    )
    (net (code "155") (name "/SD9Data0") (class "Default")
      (node (ref "SD9") (pin "6") (pinfunction "6_6") (pintype "passive"))
    )
    (net (code "156") (name "/SD9Data1") (class "Default")
      (node (ref "SD9") (pin "29") (pinfunction "29_29") (pintype "passive"))
    )
    (net (code "157") (name "/SD9Data2") (class "Default")
      (node (ref "SD9") (pin "27") (pinfunction "27_27") (pintype "passive"))
    )
    (net (code "158") (name "/SD9Data3") (class "Default")
      (node (ref "SD9") (pin "10") (pinfunction "10_10") (pintype "passive"))
    )
    (net (code "159") (name "/SD9Data4") (class "Default")
      (node (ref "SD9") (pin "4") (pinfunction "4_4") (pintype "passive"))
    )
    (net (code "160") (name "/SD9Data5") (class "Default")
      (node (ref "SD9") (pin "2") (pinfunction "2_2") (pintype "passive"))
    )
    (net (code "161") (name "/SD9Data6") (class "Default")
      (node (ref "SD9") (pin "33") (pinfunction "33_33") (pintype "passive"))
    )
    (net (code "162") (name "/SD9Data7") (class "Default")
      (node (ref "SD9") (pin "31") (pinfunction "31_31") (pintype "passive"))
    )
    (net (code "163") (name "/SD9reset") (class "Default")
      (node (ref "R9") (pin "1") (pinfunction "1_1") (pintype "passive"))
      (node (ref "SD9") (pin "12") (pinfunction "12_12") (pintype "passive"))
    )
    (net (code "164") (name "/SD10Clk") (class "Default")
      (node (ref "SD10") (pin "8") (pinfunction "8_8") (pintype "passive"))
    )
    (net (code "165") (name "/SD10Cmd") (class "Default")
      (node (ref "SD10") (pin "25") (pinfunction "25_25") (pintype "passive"))
    )
    (net (code "166") (name "/SD10Data0") (class "Default")
      (node (ref "SD10") (pin "6") (pinfunction "6_6") (pintype "passive"))
    )
    (net (code "167") (name "/SD10Data1") (class "Default")
      (node (ref "SD10") (pin "29") (pinfunction "29_29") (pintype "passive"))
    )
    (net (code "168") (name "/SD10Data2") (class "Default")
      (node (ref "SD10") (pin "27") (pinfunction "27_27") (pintype "passive"))
    )
    (net (code "169") (name "/SD10Data3") (class "Default")
      (node (ref "SD10") (pin "10") (pinfunction "10_10") (pintype "passive"))
    )
    (net (code "170") (name "/SD10Data4") (class "Default")
      (node (ref "SD10") (pin "4") (pinfunction "4_4") (pintype "passive"))
    )
    (net (code "171") (name "/SD10Data5") (class "Default")
      (node (ref "SD10") (pin "2") (pinfunction "2_2") (pintype "passive"))
    )
    (net (code "172") (name "/SD10Data6") (class "Default")
      (node (ref "SD10") (pin "33") (pinfunction "33_33") (pintype "passive"))
    )
    (net (code "173") (name "/SD10Data7") (class "Default")
      (node (ref "SD10") (pin "31") (pinfunction "31_31") (pintype "passive"))
    )
    (net (code "174") (name "/SD10reset") (class "Default")
      (node (ref "R10") (pin "1") (pinfunction "1_1") (pintype "passive"))
      (node (ref "SD10") (pin "12") (pinfunction "12_12") (pintype "passive"))
    )
    (net (code "175") (name "/SD11Clk") (class "Default")
      (node (ref "SD11") (pin "8") (pinfunction "8_8") (pintype "passive"))
    )
    (net (code "176") (name "/SD11Cmd") (class "Default")
      (node (ref "SD11") (pin "25") (pinfunction "25_25") (pintype "passive"))
    )
    (net (code "177") (name "/SD11Data0") (class "Default")
      (node (ref "SD11") (pin "6") (pinfunction "6_6") (pintype "passive"))
    )
    (net (code "178") (name "/SD11Data1") (class "Default")
      (node (ref "SD11") (pin "29") (pinfunction "29_29") (pintype "passive"))
    )
    (net (code "179") (name "/SD11Data2") (class "Default")
      (node (ref "SD11") (pin "27") (pinfunction "27_27") (pintype "passive"))
    )
    (net (code "180") (name "/SD11Data3") (class "Default")
      (node (ref "SD11") (pin "10") (pinfunction "10_10") (pintype "passive"))
    )
    (net (code "181") (name "/SD11Data4") (class "Default")
      (node (ref "SD11") (pin "4") (pinfunction "4_4") (pintype "passive"))
    )
    (net (code "182") (name "/SD11Data5") (class "Default")
      (node (ref "SD11") (pin "2") (pinfunction "2_2") (pintype "passive"))
    )
    (net (code "183") (name "/SD11Data6") (class "Default")
      (node (ref "SD11") (pin "33") (pinfunction "33_33") (pintype "passive"))
    )
    (net (code "184") (name "/SD11Data7") (class "Default")
      (node (ref "SD11") (pin "31") (pinfunction "31_31") (pintype "passive"))
    )
    (net (code "185") (name "/SD11reset") (class "Default")
      (node (ref "R11") (pin "1") (pinfunction "1_1") (pintype "passive"))
      (node (ref "SD11") (pin "12") (pinfunction "12_12") (pintype "passive"))
    )
    (net (code "186") (name "/SD12Clk") (class "Default")
      (node (ref "SD12") (pin "8") (pinfunction "8_8") (pintype "passive"))
    )
    (net (code "187") (name "/SD12Cmd") (class "Default")
      (node (ref "SD12") (pin "25") (pinfunction "25_25") (pintype "passive"))
    )
    (net (code "188") (name "/SD12Data0") (class "Default")
      (node (ref "SD12") (pin "6") (pinfunction "6_6") (pintype "passive"))
    )
    (net (code "189") (name "/SD12Data1") (class "Default")
      (node (ref "SD12") (pin "29") (pinfunction "29_29") (pintype "passive"))
    )
    (net (code "190") (name "/SD12Data2") (class "Default")
      (node (ref "SD12") (pin "27") (pinfunction "27_27") (pintype "passive"))
    )
    (net (code "191") (name "/SD12Data3") (class "Default")
      (node (ref "SD12") (pin "10") (pinfunction "10_10") (pintype "passive"))
    )
    (net (code "192") (name "/SD12Data4") (class "Default")
      (node (ref "SD12") (pin "4") (pinfunction "4_4") (pintype "passive"))
    )
    (net (code "193") (name "/SD12Data5") (class "Default")
      (node (ref "SD12") (pin "2") (pinfunction "2_2") (pintype "passive"))
    )
    (net (code "194") (name "/SD12Data6") (class "Default")
      (node (ref "SD12") (pin "33") (pinfunction "33_33") (pintype "passive"))
    )
    (net (code "195") (name "/SD12Data7") (class "Default")
      (node (ref "SD12") (pin "31") (pinfunction "31_31") (pintype "passive"))
    )
    (net (code "196") (name "/SD12reset") (class "Default")
      (node (ref "R12") (pin "1") (pinfunction "1_1") (pintype "passive"))
      (node (ref "SD12") (pin "12") (pinfunction "12_12") (pintype "passive"))
    )
    (net (code "197") (name "1V8") (class "Default")
      (node (ref "JM1") (pin "1") (pinfunction "1_1") (pintype "passive"))
    )
    (net (code "198") (name "3V3") (class "Default")
      (node (ref "C1") (pin "2") (pinfunction "2_2") (pintype "passive"))
      (node (ref "C10") (pin "2") (pinfunction "2_2") (pintype "passive"))
      (node (ref "C11") (pin "2") (pinfunction "2_2") (pintype "passive"))
      (node (ref "C12") (pin "2") (pinfunction "2_2") (pintype "passive"))
      (node (ref "C13") (pin "2") (pinfunction "2_2") (pintype "passive"))
      (node (ref "C14") (pin "2") (pinfunction "2_2") (pintype "passive"))
      (node (ref "C15") (pin "2") (pinfunction "2_2") (pintype "passive"))
      (node (ref "C16") (pin "2") (pinfunction "2_2") (pintype "passive"))
      (node (ref "C17") (pin "2") (pinfunction "2_2") (pintype "passive"))
      (node (ref "C18") (pin "2") (pinfunction "2_2") (pintype "passive"))
      (node (ref "C19") (pin "2") (pinfunction "2_2") (pintype "passive"))
      (node (ref "C2") (pin "2") (pinfunction "2_2") (pintype "passive"))
      (node (ref "C20") (pin "2") (pinfunction "2_2") (pintype "passive"))
      (node (ref "C21") (pin "2") (pinfunction "2_2") (pintype "passive"))
      (node (ref "C22") (pin "2") (pinfunction "2_2") (pintype "passive"))
      (node (ref "C23") (pin "2") (pinfunction "2_2") (pintype "passive"))
      (node (ref "C24") (pin "2") (pinfunction "2_2") (pintype "passive"))
      (node (ref "C3") (pin "2") (pinfunction "2_2") (pintype "passive"))
      (node (ref "C4") (pin "2") (pinfunction "2_2") (pintype "passive"))
      (node (ref "C5") (pin "2") (pinfunction "2_2") (pintype "passive"))
      (node (ref "C6") (pin "2") (pinfunction "2_2") (pintype "passive"))
      (node (ref "C7") (pin "2") (pinfunction "2_2") (pintype "passive"))
      (node (ref "C8") (pin "2") (pinfunction "2_2") (pintype "passive"))
      (node (ref "C9") (pin "2") (pinfunction "2_2") (pintype "passive"))
      (node (ref "JM1") (pin "3") (pinfunction "3_3") (pintype "passive"))
      (node (ref "R1") (pin "2") (pinfunction "2_2") (pintype "passive"))
      (node (ref "R10") (pin "2") (pinfunction "2_2") (pintype "passive"))
      (node (ref "R11") (pin "2") (pinfunction "2_2") (pintype "passive"))
      (node (ref "R12") (pin "2") (pinfunction "2_2") (pintype "passive"))
      (node (ref "R2") (pin "2") (pinfunction "2_2") (pintype "passive"))
      (node (ref "R3") (pin "2") (pinfunction "2_2") (pintype "passive"))
      (node (ref "R4") (pin "2") (pinfunction "2_2") (pintype "passive"))
      (node (ref "R5") (pin "2") (pinfunction "2_2") (pintype "passive"))
      (node (ref "R6") (pin "2") (pinfunction "2_2") (pintype "passive"))
      (node (ref "R7") (pin "2") (pinfunction "2_2") (pintype "passive"))
      (node (ref "R8") (pin "2") (pinfunction "2_2") (pintype "passive"))
      (node (ref "R9") (pin "2") (pinfunction "2_2") (pintype "passive"))
      (node (ref "SD1") (pin "20") (pinfunction "20_20") (pintype "passive"))
      (node (ref "SD1") (pin "21") (pinfunction "21_21") (pintype "passive"))
      (node (ref "SD1") (pin "22") (pinfunction "22_22") (pintype "passive"))
      (node (ref "SD1") (pin "23") (pinfunction "23_23") (pintype "passive"))
      (node (ref "SD10") (pin "20") (pinfunction "20_20") (pintype "passive"))
      (node (ref "SD10") (pin "21") (pinfunction "21_21") (pintype "passive"))
      (node (ref "SD10") (pin "22") (pinfunction "22_22") (pintype "passive"))
      (node (ref "SD10") (pin "23") (pinfunction "23_23") (pintype "passive"))
      (node (ref "SD11") (pin "20") (pinfunction "20_20") (pintype "passive"))
      (node (ref "SD11") (pin "21") (pinfunction "21_21") (pintype "passive"))
      (node (ref "SD11") (pin "22") (pinfunction "22_22") (pintype "passive"))
      (node (ref "SD11") (pin "23") (pinfunction "23_23") (pintype "passive"))
      (node (ref "SD12") (pin "20") (pinfunction "20_20") (pintype "passive"))
      (node (ref "SD12") (pin "21") (pinfunction "21_21") (pintype "passive"))
      (node (ref "SD12") (pin "22") (pinfunction "22_22") (pintype "passive"))
      (node (ref "SD12") (pin "23") (pinfunction "23_23") (pintype "passive"))
      (node (ref "SD2") (pin "20") (pinfunction "20_20") (pintype "passive"))
      (node (ref "SD2") (pin "21") (pinfunction "21_21") (pintype "passive"))
      (node (ref "SD2") (pin "22") (pinfunction "22_22") (pintype "passive"))
      (node (ref "SD2") (pin "23") (pinfunction "23_23") (pintype "passive"))
      (node (ref "SD3") (pin "20") (pinfunction "20_20") (pintype "passive"))
      (node (ref "SD3") (pin "21") (pinfunction "21_21") (pintype "passive"))
      (node (ref "SD3") (pin "22") (pinfunction "22_22") (pintype "passive"))
      (node (ref "SD3") (pin "23") (pinfunction "23_23") (pintype "passive"))
      (node (ref "SD4") (pin "20") (pinfunction "20_20") (pintype "passive"))
      (node (ref "SD4") (pin "21") (pinfunction "21_21") (pintype "passive"))
      (node (ref "SD4") (pin "22") (pinfunction "22_22") (pintype "passive"))
      (node (ref "SD4") (pin "23") (pinfunction "23_23") (pintype "passive"))
      (node (ref "SD5") (pin "20") (pinfunction "20_20") (pintype "passive"))
      (node (ref "SD5") (pin "21") (pinfunction "21_21") (pintype "passive"))
      (node (ref "SD5") (pin "22") (pinfunction "22_22") (pintype "passive"))
      (node (ref "SD5") (pin "23") (pinfunction "23_23") (pintype "passive"))
      (node (ref "SD6") (pin "20") (pinfunction "20_20") (pintype "passive"))
      (node (ref "SD6") (pin "21") (pinfunction "21_21") (pintype "passive"))
      (node (ref "SD6") (pin "22") (pinfunction "22_22") (pintype "passive"))
      (node (ref "SD6") (pin "23") (pinfunction "23_23") (pintype "passive"))
      (node (ref "SD7") (pin "20") (pinfunction "20_20") (pintype "passive"))
      (node (ref "SD7") (pin "21") (pinfunction "21_21") (pintype "passive"))
      (node (ref "SD7") (pin "22") (pinfunction "22_22") (pintype "passive"))
      (node (ref "SD7") (pin "23") (pinfunction "23_23") (pintype "passive"))
      (node (ref "SD8") (pin "20") (pinfunction "20_20") (pintype "passive"))
      (node (ref "SD8") (pin "21") (pinfunction "21_21") (pintype "passive"))
      (node (ref "SD8") (pin "22") (pinfunction "22_22") (pintype "passive"))
      (node (ref "SD8") (pin "23") (pinfunction "23_23") (pintype "passive"))
      (node (ref "SD9") (pin "20") (pinfunction "20_20") (pintype "passive"))
      (node (ref "SD9") (pin "21") (pinfunction "21_21") (pintype "passive"))
      (node (ref "SD9") (pin "22") (pinfunction "22_22") (pintype "passive"))
      (node (ref "SD9") (pin "23") (pinfunction "23_23") (pintype "passive"))
    )
    (net (code "199") (name "GND") (class "Default")
      (node (ref "C1") (pin "1") (pinfunction "1_1") (pintype "passive"))
      (node (ref "C10") (pin "1") (pinfunction "1_1") (pintype "passive"))
      (node (ref "C11") (pin "1") (pinfunction "1_1") (pintype "passive"))
      (node (ref "C12") (pin "1") (pinfunction "1_1") (pintype "passive"))
      (node (ref "C13") (pin "1") (pinfunction "1_1") (pintype "passive"))
      (node (ref "C14") (pin "1") (pinfunction "1_1") (pintype "passive"))
      (node (ref "C15") (pin "1") (pinfunction "1_1") (pintype "passive"))
      (node (ref "C16") (pin "1") (pinfunction "1_1") (pintype "passive"))
      (node (ref "C17") (pin "1") (pinfunction "1_1") (pintype "passive"))
      (node (ref "C18") (pin "1") (pinfunction "1_1") (pintype "passive"))
      (node (ref "C19") (pin "1") (pinfunction "1_1") (pintype "passive"))
      (node (ref "C2") (pin "1") (pinfunction "1_1") (pintype "passive"))
      (node (ref "C20") (pin "1") (pinfunction "1_1") (pintype "passive"))
      (node (ref "C21") (pin "1") (pinfunction "1_1") (pintype "passive"))
      (node (ref "C22") (pin "1") (pinfunction "1_1") (pintype "passive"))
      (node (ref "C23") (pin "1") (pinfunction "1_1") (pintype "passive"))
      (node (ref "C24") (pin "1") (pinfunction "1_1") (pintype "passive"))
      (node (ref "C3") (pin "1") (pinfunction "1_1") (pintype "passive"))
      (node (ref "C4") (pin "1") (pinfunction "1_1") (pintype "passive"))
      (node (ref "C5") (pin "1") (pinfunction "1_1") (pintype "passive"))
      (node (ref "C6") (pin "1") (pinfunction "1_1") (pintype "passive"))
      (node (ref "C7") (pin "1") (pinfunction "1_1") (pintype "passive"))
      (node (ref "C8") (pin "1") (pinfunction "1_1") (pintype "passive"))
      (node (ref "C9") (pin "1") (pinfunction "1_1") (pintype "passive"))
      (node (ref "P1") (pin "11") (pinfunction "11_11") (pintype "passive"))
      (node (ref "P1") (pin "12") (pinfunction "12_12") (pintype "passive"))
      (node (ref "P1") (pin "21") (pinfunction "21_21") (pintype "passive"))
      (node (ref "P1") (pin "22") (pinfunction "22_22") (pintype "passive"))
      (node (ref "P1") (pin "31") (pinfunction "31_31") (pintype "passive"))
      (node (ref "P1") (pin "32") (pinfunction "32_32") (pintype "passive"))
      (node (ref "P1") (pin "41") (pinfunction "41_41") (pintype "passive"))
      (node (ref "P1") (pin "42") (pinfunction "42_42") (pintype "passive"))
      (node (ref "P1") (pin "51") (pinfunction "51_51") (pintype "passive"))
      (node (ref "P1") (pin "52") (pinfunction "52_52") (pintype "passive"))
      (node (ref "P17") (pin "11") (pinfunction "11_11") (pintype "bidirectional"))
      (node (ref "P17") (pin "13") (pinfunction "13_13") (pintype "bidirectional"))
      (node (ref "P17") (pin "3") (pinfunction "3_3") (pintype "bidirectional"))
      (node (ref "P17") (pin "5") (pinfunction "5_5") (pintype "bidirectional"))
      (node (ref "P17") (pin "7") (pinfunction "7_7") (pintype "bidirectional"))
      (node (ref "P17") (pin "9") (pinfunction "9_9") (pintype "bidirectional"))
      (node (ref "P18") (pin "2") (pinfunction "2_2") (pintype "bidirectional"))
      (node (ref "P2") (pin "11") (pinfunction "11_11") (pintype "passive"))
      (node (ref "P2") (pin "12") (pinfunction "12_12") (pintype "passive"))
      (node (ref "P2") (pin "21") (pinfunction "21_21") (pintype "passive"))
      (node (ref "P2") (pin "22") (pinfunction "22_22") (pintype "passive"))
      (node (ref "P2") (pin "31") (pinfunction "31_31") (pintype "passive"))
      (node (ref "P2") (pin "32") (pinfunction "32_32") (pintype "passive"))
      (node (ref "P2") (pin "41") (pinfunction "41_41") (pintype "passive"))
      (node (ref "P2") (pin "42") (pinfunction "42_42") (pintype "passive"))
      (node (ref "P2") (pin "51") (pinfunction "51_51") (pintype "passive"))
      (node (ref "P2") (pin "52") (pinfunction "52_52") (pintype "passive"))
      (node (ref "P3") (pin "11") (pinfunction "11_11") (pintype "passive"))
      (node (ref "P3") (pin "12") (pinfunction "12_12") (pintype "passive"))
      (node (ref "P3") (pin "21") (pinfunction "21_21") (pintype "passive"))
      (node (ref "P3") (pin "22") (pinfunction "22_22") (pintype "passive"))
      (node (ref "P3") (pin "31") (pinfunction "31_31") (pintype "passive"))
      (node (ref "P3") (pin "32") (pinfunction "32_32") (pintype "passive"))
      (node (ref "P3") (pin "35") (pinfunction "35_35") (pintype "passive"))
      (node (ref "P3") (pin "36") (pinfunction "36_36") (pintype "passive"))
      (node (ref "P3") (pin "41") (pinfunction "41_41") (pintype "passive"))
      (node (ref "P3") (pin "42") (pinfunction "42_42") (pintype "passive"))
      (node (ref "P3") (pin "51") (pinfunction "51_51") (pintype "passive"))
      (node (ref "P3") (pin "52") (pinfunction "52_52") (pintype "passive"))
      (node (ref "P4") (pin "11") (pinfunction "11_11") (pintype "passive"))
      (node (ref "P4") (pin "12") (pinfunction "12_12") (pintype "passive"))
      (node (ref "P4") (pin "21") (pinfunction "21_21") (pintype "passive"))
      (node (ref "P4") (pin "22") (pinfunction "22_22") (pintype "passive"))
      (node (ref "P4") (pin "31") (pinfunction "31_31") (pintype "passive"))
      (node (ref "P4") (pin "32") (pinfunction "32_32") (pintype "passive"))
      (node (ref "P4") (pin "41") (pinfunction "41_41") (pintype "passive"))
      (node (ref "P4") (pin "42") (pinfunction "42_42") (pintype "passive"))
      (node (ref "P4") (pin "51") (pinfunction "51_51") (pintype "passive"))
      (node (ref "P4") (pin "52") (pinfunction "52_52") (pintype "passive"))
      (node (ref "SD1") (pin "1") (pinfunction "1_1") (pintype "passive"))
      (node (ref "SD1") (pin "11") (pinfunction "11_11") (pintype "passive"))
      (node (ref "SD1") (pin "13") (pinfunction "13_13") (pintype "passive"))
      (node (ref "SD1") (pin "14") (pinfunction "14_14") (pintype "passive"))
      (node (ref "SD1") (pin "16") (pinfunction "16_16") (pintype "passive"))
      (node (ref "SD1") (pin "17") (pinfunction "17_17") (pintype "passive"))
      (node (ref "SD1") (pin "18") (pinfunction "18_18") (pintype "passive"))
      (node (ref "SD1") (pin "19") (pinfunction "19_19") (pintype "passive"))
      (node (ref "SD1") (pin "24") (pinfunction "24_24") (pintype "passive"))
      (node (ref "SD1") (pin "26") (pinfunction "26_26") (pintype "passive"))
      (node (ref "SD1") (pin "28") (pinfunction "28_28") (pintype "passive"))
      (node (ref "SD1") (pin "3") (pinfunction "3_3") (pintype "passive"))
      (node (ref "SD1") (pin "30") (pinfunction "30_30") (pintype "passive"))
      (node (ref "SD1") (pin "32") (pinfunction "32_32") (pintype "passive"))
      (node (ref "SD1") (pin "34") (pinfunction "34_34") (pintype "passive"))
      (node (ref "SD1") (pin "5") (pinfunction "5_5") (pintype "passive"))
      (node (ref "SD1") (pin "7") (pinfunction "7_7") (pintype "passive"))
      (node (ref "SD1") (pin "9") (pinfunction "9_9") (pintype "passive"))
      (node (ref "SD10") (pin "1") (pinfunction "1_1") (pintype "passive"))
      (node (ref "SD10") (pin "11") (pinfunction "11_11") (pintype "passive"))
      (node (ref "SD10") (pin "13") (pinfunction "13_13") (pintype "passive"))
      (node (ref "SD10") (pin "14") (pinfunction "14_14") (pintype "passive"))
      (node (ref "SD10") (pin "16") (pinfunction "16_16") (pintype "passive"))
      (node (ref "SD10") (pin "17") (pinfunction "17_17") (pintype "passive"))
      (node (ref "SD10") (pin "18") (pinfunction "18_18") (pintype "passive"))
      (node (ref "SD10") (pin "19") (pinfunction "19_19") (pintype "passive"))
      (node (ref "SD10") (pin "24") (pinfunction "24_24") (pintype "passive"))
      (node (ref "SD10") (pin "26") (pinfunction "26_26") (pintype "passive"))
      (node (ref "SD10") (pin "28") (pinfunction "28_28") (pintype "passive"))
      (node (ref "SD10") (pin "3") (pinfunction "3_3") (pintype "passive"))
      (node (ref "SD10") (pin "30") (pinfunction "30_30") (pintype "passive"))
      (node (ref "SD10") (pin "32") (pinfunction "32_32") (pintype "passive"))
      (node (ref "SD10") (pin "34") (pinfunction "34_34") (pintype "passive"))
      (node (ref "SD10") (pin "5") (pinfunction "5_5") (pintype "passive"))
      (node (ref "SD10") (pin "7") (pinfunction "7_7") (pintype "passive"))
      (node (ref "SD10") (pin "9") (pinfunction "9_9") (pintype "passive"))
      (node (ref "SD11") (pin "1") (pinfunction "1_1") (pintype "passive"))
      (node (ref "SD11") (pin "11") (pinfunction "11_11") (pintype "passive"))
      (node (ref "SD11") (pin "13") (pinfunction "13_13") (pintype "passive"))
      (node (ref "SD11") (pin "14") (pinfunction "14_14") (pintype "passive"))
      (node (ref "SD11") (pin "16") (pinfunction "16_16") (pintype "passive"))
      (node (ref "SD11") (pin "17") (pinfunction "17_17") (pintype "passive"))
      (node (ref "SD11") (pin "18") (pinfunction "18_18") (pintype "passive"))
      (node (ref "SD11") (pin "19") (pinfunction "19_19") (pintype "passive"))
      (node (ref "SD11") (pin "24") (pinfunction "24_24") (pintype "passive"))
      (node (ref "SD11") (pin "26") (pinfunction "26_26") (pintype "passive"))
      (node (ref "SD11") (pin "28") (pinfunction "28_28") (pintype "passive"))
      (node (ref "SD11") (pin "3") (pinfunction "3_3") (pintype "passive"))
      (node (ref "SD11") (pin "30") (pinfunction "30_30") (pintype "passive"))
      (node (ref "SD11") (pin "32") (pinfunction "32_32") (pintype "passive"))
      (node (ref "SD11") (pin "34") (pinfunction "34_34") (pintype "passive"))
      (node (ref "SD11") (pin "5") (pinfunction "5_5") (pintype "passive"))
      (node (ref "SD11") (pin "7") (pinfunction "7_7") (pintype "passive"))
      (node (ref "SD11") (pin "9") (pinfunction "9_9") (pintype "passive"))
      (node (ref "SD12") (pin "1") (pinfunction "1_1") (pintype "passive"))
      (node (ref "SD12") (pin "11") (pinfunction "11_11") (pintype "passive"))
      (node (ref "SD12") (pin "13") (pinfunction "13_13") (pintype "passive"))
      (node (ref "SD12") (pin "14") (pinfunction "14_14") (pintype "passive"))
      (node (ref "SD12") (pin "16") (pinfunction "16_16") (pintype "passive"))
      (node (ref "SD12") (pin "17") (pinfunction "17_17") (pintype "passive"))
      (node (ref "SD12") (pin "18") (pinfunction "18_18") (pintype "passive"))
      (node (ref "SD12") (pin "19") (pinfunction "19_19") (pintype "passive"))
      (node (ref "SD12") (pin "24") (pinfunction "24_24") (pintype "passive"))
      (node (ref "SD12") (pin "26") (pinfunction "26_26") (pintype "passive"))
      (node (ref "SD12") (pin "28") (pinfunction "28_28") (pintype "passive"))
      (node (ref "SD12") (pin "3") (pinfunction "3_3") (pintype "passive"))
      (node (ref "SD12") (pin "30") (pinfunction "30_30") (pintype "passive"))
      (node (ref "SD12") (pin "32") (pinfunction "32_32") (pintype "passive"))
      (node (ref "SD12") (pin "34") (pinfunction "34_34") (pintype "passive"))
      (node (ref "SD12") (pin "5") (pinfunction "5_5") (pintype "passive"))
      (node (ref "SD12") (pin "7") (pinfunction "7_7") (pintype "passive"))
      (node (ref "SD12") (pin "9") (pinfunction "9_9") (pintype "passive"))
      (node (ref "SD2") (pin "1") (pinfunction "1_1") (pintype "passive"))
      (node (ref "SD2") (pin "11") (pinfunction "11_11") (pintype "passive"))
      (node (ref "SD2") (pin "13") (pinfunction "13_13") (pintype "passive"))
      (node (ref "SD2") (pin "14") (pinfunction "14_14") (pintype "passive"))
      (node (ref "SD2") (pin "16") (pinfunction "16_16") (pintype "passive"))
      (node (ref "SD2") (pin "17") (pinfunction "17_17") (pintype "passive"))
      (node (ref "SD2") (pin "18") (pinfunction "18_18") (pintype "passive"))
      (node (ref "SD2") (pin "19") (pinfunction "19_19") (pintype "passive"))
      (node (ref "SD2") (pin "24") (pinfunction "24_24") (pintype "passive"))
      (node (ref "SD2") (pin "26") (pinfunction "26_26") (pintype "passive"))
      (node (ref "SD2") (pin "28") (pinfunction "28_28") (pintype "passive"))
      (node (ref "SD2") (pin "3") (pinfunction "3_3") (pintype "passive"))
      (node (ref "SD2") (pin "30") (pinfunction "30_30") (pintype "passive"))
      (node (ref "SD2") (pin "32") (pinfunction "32_32") (pintype "passive"))
      (node (ref "SD2") (pin "34") (pinfunction "34_34") (pintype "passive"))
      (node (ref "SD2") (pin "5") (pinfunction "5_5") (pintype "passive"))
      (node (ref "SD2") (pin "7") (pinfunction "7_7") (pintype "passive"))
      (node (ref "SD2") (pin "9") (pinfunction "9_9") (pintype "passive"))
      (node (ref "SD3") (pin "1") (pinfunction "1_1") (pintype "passive"))
      (node (ref "SD3") (pin "11") (pinfunction "11_11") (pintype "passive"))
      (node (ref "SD3") (pin "13") (pinfunction "13_13") (pintype "passive"))
      (node (ref "SD3") (pin "14") (pinfunction "14_14") (pintype "passive"))
      (node (ref "SD3") (pin "16") (pinfunction "16_16") (pintype "passive"))
      (node (ref "SD3") (pin "17") (pinfunction "17_17") (pintype "passive"))
      (node (ref "SD3") (pin "18") (pinfunction "18_18") (pintype "passive"))
      (node (ref "SD3") (pin "19") (pinfunction "19_19") (pintype "passive"))
      (node (ref "SD3") (pin "24") (pinfunction "24_24") (pintype "passive"))
      (node (ref "SD3") (pin "26") (pinfunction "26_26") (pintype "passive"))
      (node (ref "SD3") (pin "28") (pinfunction "28_28") (pintype "passive"))
      (node (ref "SD3") (pin "3") (pinfunction "3_3") (pintype "passive"))
      (node (ref "SD3") (pin "30") (pinfunction "30_30") (pintype "passive"))
      (node (ref "SD3") (pin "32") (pinfunction "32_32") (pintype "passive"))
      (node (ref "SD3") (pin "34") (pinfunction "34_34") (pintype "passive"))
      (node (ref "SD3") (pin "5") (pinfunction "5_5") (pintype "passive"))
      (node (ref "SD3") (pin "7") (pinfunction "7_7") (pintype "passive"))
      (node (ref "SD3") (pin "9") (pinfunction "9_9") (pintype "passive"))
      (node (ref "SD4") (pin "1") (pinfunction "1_1") (pintype "passive"))
      (node (ref "SD4") (pin "11") (pinfunction "11_11") (pintype "passive"))
      (node (ref "SD4") (pin "13") (pinfunction "13_13") (pintype "passive"))
      (node (ref "SD4") (pin "14") (pinfunction "14_14") (pintype "passive"))
      (node (ref "SD4") (pin "16") (pinfunction "16_16") (pintype "passive"))
      (node (ref "SD4") (pin "17") (pinfunction "17_17") (pintype "passive"))
      (node (ref "SD4") (pin "18") (pinfunction "18_18") (pintype "passive"))
      (node (ref "SD4") (pin "19") (pinfunction "19_19") (pintype "passive"))
      (node (ref "SD4") (pin "24") (pinfunction "24_24") (pintype "passive"))
      (node (ref "SD4") (pin "26") (pinfunction "26_26") (pintype "passive"))
      (node (ref "SD4") (pin "28") (pinfunction "28_28") (pintype "passive"))
      (node (ref "SD4") (pin "3") (pinfunction "3_3") (pintype "passive"))
      (node (ref "SD4") (pin "30") (pinfunction "30_30") (pintype "passive"))
      (node (ref "SD4") (pin "32") (pinfunction "32_32") (pintype "passive"))
      (node (ref "SD4") (pin "34") (pinfunction "34_34") (pintype "passive"))
      (node (ref "SD4") (pin "5") (pinfunction "5_5") (pintype "passive"))
      (node (ref "SD4") (pin "7") (pinfunction "7_7") (pintype "passive"))
      (node (ref "SD4") (pin "9") (pinfunction "9_9") (pintype "passive"))
      (node (ref "SD5") (pin "1") (pinfunction "1_1") (pintype "passive"))
      (node (ref "SD5") (pin "11") (pinfunction "11_11") (pintype "passive"))
      (node (ref "SD5") (pin "13") (pinfunction "13_13") (pintype "passive"))
      (node (ref "SD5") (pin "14") (pinfunction "14_14") (pintype "passive"))
      (node (ref "SD5") (pin "16") (pinfunction "16_16") (pintype "passive"))
      (node (ref "SD5") (pin "17") (pinfunction "17_17") (pintype "passive"))
      (node (ref "SD5") (pin "18") (pinfunction "18_18") (pintype "passive"))
      (node (ref "SD5") (pin "19") (pinfunction "19_19") (pintype "passive"))
      (node (ref "SD5") (pin "24") (pinfunction "24_24") (pintype "passive"))
      (node (ref "SD5") (pin "26") (pinfunction "26_26") (pintype "passive"))
      (node (ref "SD5") (pin "28") (pinfunction "28_28") (pintype "passive"))
      (node (ref "SD5") (pin "3") (pinfunction "3_3") (pintype "passive"))
      (node (ref "SD5") (pin "30") (pinfunction "30_30") (pintype "passive"))
      (node (ref "SD5") (pin "32") (pinfunction "32_32") (pintype "passive"))
      (node (ref "SD5") (pin "34") (pinfunction "34_34") (pintype "passive"))
      (node (ref "SD5") (pin "5") (pinfunction "5_5") (pintype "passive"))
      (node (ref "SD5") (pin "7") (pinfunction "7_7") (pintype "passive"))
      (node (ref "SD5") (pin "9") (pinfunction "9_9") (pintype "passive"))
      (node (ref "SD6") (pin "1") (pinfunction "1_1") (pintype "passive"))
      (node (ref "SD6") (pin "11") (pinfunction "11_11") (pintype "passive"))
      (node (ref "SD6") (pin "13") (pinfunction "13_13") (pintype "passive"))
      (node (ref "SD6") (pin "14") (pinfunction "14_14") (pintype "passive"))
      (node (ref "SD6") (pin "16") (pinfunction "16_16") (pintype "passive"))
      (node (ref "SD6") (pin "17") (pinfunction "17_17") (pintype "passive"))
      (node (ref "SD6") (pin "18") (pinfunction "18_18") (pintype "passive"))
      (node (ref "SD6") (pin "19") (pinfunction "19_19") (pintype "passive"))
      (node (ref "SD6") (pin "24") (pinfunction "24_24") (pintype "passive"))
      (node (ref "SD6") (pin "26") (pinfunction "26_26") (pintype "passive"))
      (node (ref "SD6") (pin "28") (pinfunction "28_28") (pintype "passive"))
      (node (ref "SD6") (pin "3") (pinfunction "3_3") (pintype "passive"))
      (node (ref "SD6") (pin "30") (pinfunction "30_30") (pintype "passive"))
      (node (ref "SD6") (pin "32") (pinfunction "32_32") (pintype "passive"))
      (node (ref "SD6") (pin "34") (pinfunction "34_34") (pintype "passive"))
      (node (ref "SD6") (pin "5") (pinfunction "5_5") (pintype "passive"))
      (node (ref "SD6") (pin "7") (pinfunction "7_7") (pintype "passive"))
      (node (ref "SD6") (pin "9") (pinfunction "9_9") (pintype "passive"))
      (node (ref "SD7") (pin "1") (pinfunction "1_1") (pintype "passive"))
      (node (ref "SD7") (pin "11") (pinfunction "11_11") (pintype "passive"))
      (node (ref "SD7") (pin "13") (pinfunction "13_13") (pintype "passive"))
      (node (ref "SD7") (pin "14") (pinfunction "14_14") (pintype "passive"))
      (node (ref "SD7") (pin "16") (pinfunction "16_16") (pintype "passive"))
      (node (ref "SD7") (pin "17") (pinfunction "17_17") (pintype "passive"))
      (node (ref "SD7") (pin "18") (pinfunction "18_18") (pintype "passive"))
      (node (ref "SD7") (pin "19") (pinfunction "19_19") (pintype "passive"))
      (node (ref "SD7") (pin "24") (pinfunction "24_24") (pintype "passive"))
      (node (ref "SD7") (pin "26") (pinfunction "26_26") (pintype "passive"))
      (node (ref "SD7") (pin "28") (pinfunction "28_28") (pintype "passive"))
      (node (ref "SD7") (pin "3") (pinfunction "3_3") (pintype "passive"))
      (node (ref "SD7") (pin "30") (pinfunction "30_30") (pintype "passive"))
      (node (ref "SD7") (pin "32") (pinfunction "32_32") (pintype "passive"))
      (node (ref "SD7") (pin "34") (pinfunction "34_34") (pintype "passive"))
      (node (ref "SD7") (pin "5") (pinfunction "5_5") (pintype "passive"))
      (node (ref "SD7") (pin "7") (pinfunction "7_7") (pintype "passive"))
      (node (ref "SD7") (pin "9") (pinfunction "9_9") (pintype "passive"))
      (node (ref "SD8") (pin "1") (pinfunction "1_1") (pintype "passive"))
      (node (ref "SD8") (pin "11") (pinfunction "11_11") (pintype "passive"))
      (node (ref "SD8") (pin "13") (pinfunction "13_13") (pintype "passive"))
      (node (ref "SD8") (pin "14") (pinfunction "14_14") (pintype "passive"))
      (node (ref "SD8") (pin "16") (pinfunction "16_16") (pintype "passive"))
      (node (ref "SD8") (pin "17") (pinfunction "17_17") (pintype "passive"))
      (node (ref "SD8") (pin "18") (pinfunction "18_18") (pintype "passive"))
      (node (ref "SD8") (pin "19") (pinfunction "19_19") (pintype "passive"))
      (node (ref "SD8") (pin "24") (pinfunction "24_24") (pintype "passive"))
      (node (ref "SD8") (pin "26") (pinfunction "26_26") (pintype "passive"))
      (node (ref "SD8") (pin "28") (pinfunction "28_28") (pintype "passive"))
      (node (ref "SD8") (pin "3") (pinfunction "3_3") (pintype "passive"))
      (node (ref "SD8") (pin "30") (pinfunction "30_30") (pintype "passive"))
      (node (ref "SD8") (pin "32") (pinfunction "32_32") (pintype "passive"))
      (node (ref "SD8") (pin "34") (pinfunction "34_34") (pintype "passive"))
      (node (ref "SD8") (pin "5") (pinfunction "5_5") (pintype "passive"))
      (node (ref "SD8") (pin "7") (pinfunction "7_7") (pintype "passive"))
      (node (ref "SD8") (pin "9") (pinfunction "9_9") (pintype "passive"))
      (node (ref "SD9") (pin "1") (pinfunction "1_1") (pintype "passive"))
      (node (ref "SD9") (pin "11") (pinfunction "11_11") (pintype "passive"))
      (node (ref "SD9") (pin "13") (pinfunction "13_13") (pintype "passive"))
      (node (ref "SD9") (pin "14") (pinfunction "14_14") (pintype "passive"))
      (node (ref "SD9") (pin "16") (pinfunction "16_16") (pintype "passive"))
      (node (ref "SD9") (pin "17") (pinfunction "17_17") (pintype "passive"))
      (node (ref "SD9") (pin "18") (pinfunction "18_18") (pintype "passive"))
      (node (ref "SD9") (pin "19") (pinfunction "19_19") (pintype "passive"))
      (node (ref "SD9") (pin "24") (pinfunction "24_24") (pintype "passive"))
      (node (ref "SD9") (pin "26") (pinfunction "26_26") (pintype "passive"))
      (node (ref "SD9") (pin "28") (pinfunction "28_28") (pintype "passive"))
      (node (ref "SD9") (pin "3") (pinfunction "3_3") (pintype "passive"))
      (node (ref "SD9") (pin "30") (pinfunction "30_30") (pintype "passive"))
      (node (ref "SD9") (pin "32") (pinfunction "32_32") (pintype "passive"))
      (node (ref "SD9") (pin "34") (pinfunction "34_34") (pintype "passive"))
      (node (ref "SD9") (pin "5") (pinfunction "5_5") (pintype "passive"))
      (node (ref "SD9") (pin "7") (pinfunction "7_7") (pintype "passive"))
      (node (ref "SD9") (pin "9") (pinfunction "9_9") (pintype "passive"))
    )
    (net (code "200") (name "Net-(JM1-Pad2)") (class "Default")
      (node (ref "JM1") (pin "2") (pinfunction "2_2") (pintype "passive"))
      (node (ref "P17") (pin "2") (pinfunction "2_2") (pintype "bidirectional"))
    )
    (net (code "201") (name "Net-(P17-Pad4)") (class "Default")
      (node (ref "P17") (pin "4") (pinfunction "4_4") (pintype "bidirectional"))
      (node (ref "R34") (pin "2") (pinfunction "2_2") (pintype "passive"))
    )
    (net (code "202") (name "Net-(P17-Pad6)") (class "Default")
      (node (ref "P17") (pin "6") (pinfunction "6_6") (pintype "bidirectional"))
      (node (ref "R35") (pin "2") (pinfunction "2_2") (pintype "passive"))
    )
    (net (code "203") (name "Net-(P17-Pad8)") (class "Default")
      (node (ref "P17") (pin "8") (pinfunction "8_8") (pintype "bidirectional"))
      (node (ref "R36") (pin "2") (pinfunction "2_2") (pintype "passive"))
    )
    (net (code "204") (name "Net-(P17-Pad10)") (class "Default")
      (node (ref "P17") (pin "10") (pinfunction "10_10") (pintype "bidirectional"))
      (node (ref "R37") (pin "2") (pinfunction "2_2") (pintype "passive"))
    )
    (net (code "205") (name "VDDGPIO") (class "Default")
      (node (ref "P1") (pin "1") (pinfunction "1_1") (pintype "passive"))
      (node (ref "P1") (pin "2") (pinfunction "2_2") (pintype "passive"))
    )
    (net (code "206") (name "Vin") (class "Default")
      (node (ref "P18") (pin "1") (pinfunction "1_1") (pintype "bidirectional"))
    )
    (net (code "207") (name "unconnected-(P1-PadHOLE)") (class "Default")
      (node (ref "P1") (pin "HOLE") (pinfunction "HOLE_HOLE") (pintype "passive"))
    )
    (net (code "208") (name "unconnected-(P2-Pad1)") (class "Default")
      (node (ref "P2") (pin "1") (pinfunction "1_1") (pintype "passive"))
    )
    (net (code "209") (name "unconnected-(P2-Pad2)") (class "Default")
      (node (ref "P2") (pin "2") (pinfunction "2_2") (pintype "passive"))
    )
    (net (code "210") (name "unconnected-(P2-Pad3)") (class "Default")
      (node (ref "P2") (pin "3") (pinfunction "3_3") (pintype "passive"))
    )
    (net (code "211") (name "unconnected-(P2-Pad4)") (class "Default")
      (node (ref "P2") (pin "4") (pinfunction "4_4") (pintype "passive"))
    )
    (net (code "212") (name "unconnected-(P2-Pad5)") (class "Default")
      (node (ref "P2") (pin "5") (pinfunction "5_5") (pintype "passive"))
    )
    (net (code "213") (name "unconnected-(P2-Pad6)") (class "Default")
      (node (ref "P2") (pin "6") (pinfunction "6_6") (pintype "passive"))
    )
    (net (code "214") (name "unconnected-(P2-Pad7)") (class "Default")
      (node (ref "P2") (pin "7") (pinfunction "7_7") (pintype "passive"))
    )
    (net (code "215") (name "unconnected-(P2-Pad8)") (class "Default")
      (node (ref "P2") (pin "8") (pinfunction "8_8") (pintype "passive"))
    )
    (net (code "216") (name "unconnected-(P2-Pad9)") (class "Default")
      (node (ref "P2") (pin "9") (pinfunction "9_9") (pintype "passive"))
    )
    (net (code "217") (name "unconnected-(P2-Pad10)") (class "Default")
      (node (ref "P2") (pin "10") (pinfunction "10_10") (pintype "passive"))
    )
    (net (code "218") (name "unconnected-(P2-Pad13)") (class "Default")
      (node (ref "P2") (pin "13") (pinfunction "13_13") (pintype "passive"))
    )
    (net (code "219") (name "unconnected-(P2-Pad14)") (class "Default")
      (node (ref "P2") (pin "14") (pinfunction "14_14") (pintype "passive"))
    )
    (net (code "220") (name "unconnected-(P2-Pad15)") (class "Default")
      (node (ref "P2") (pin "15") (pinfunction "15_15") (pintype "passive"))
    )
    (net (code "221") (name "unconnected-(P2-Pad16)") (class "Default")
      (node (ref "P2") (pin "16") (pinfunction "16_16") (pintype "passive"))
    )
    (net (code "222") (name "unconnected-(P2-Pad17)") (class "Default")
      (node (ref "P2") (pin "17") (pinfunction "17_17") (pintype "passive"))
    )
    (net (code "223") (name "unconnected-(P2-Pad18)") (class "Default")
      (node (ref "P2") (pin "18") (pinfunction "18_18") (pintype "passive"))
    )
    (net (code "224") (name "unconnected-(P2-Pad19)") (class "Default")
      (node (ref "P2") (pin "19") (pinfunction "19_19") (pintype "passive"))
    )
    (net (code "225") (name "unconnected-(P2-Pad20)") (class "Default")
      (node (ref "P2") (pin "20") (pinfunction "20_20") (pintype "passive"))
    )
    (net (code "226") (name "unconnected-(P2-Pad23)") (class "Default")
      (node (ref "P2") (pin "23") (pinfunction "23_23") (pintype "passive"))
    )
    (net (code "227") (name "unconnected-(P2-Pad24)") (class "Default")
      (node (ref "P2") (pin "24") (pinfunction "24_24") (pintype "passive"))
    )
    (net (code "228") (name "unconnected-(P2-Pad25)") (class "Default")
      (node (ref "P2") (pin "25") (pinfunction "25_25") (pintype "passive"))
    )
    (net (code "229") (name "unconnected-(P2-Pad26)") (class "Default")
      (node (ref "P2") (pin "26") (pinfunction "26_26") (pintype "passive"))
    )
    (net (code "230") (name "unconnected-(P2-Pad27)") (class "Default")
      (node (ref "P2") (pin "27") (pinfunction "27_27") (pintype "passive"))
    )
    (net (code "231") (name "unconnected-(P2-Pad28)") (class "Default")
      (node (ref "P2") (pin "28") (pinfunction "28_28") (pintype "passive"))
    )
    (net (code "232") (name "unconnected-(P2-Pad29)") (class "Default")
      (node (ref "P2") (pin "29") (pinfunction "29_29") (pintype "passive"))
    )
    (net (code "233") (name "unconnected-(P2-Pad30)") (class "Default")
      (node (ref "P2") (pin "30") (pinfunction "30_30") (pintype "passive"))
    )
    (net (code "234") (name "unconnected-(P2-Pad33)") (class "Default")
      (node (ref "P2") (pin "33") (pinfunction "33_33") (pintype "passive"))
    )
    (net (code "235") (name "unconnected-(P2-Pad34)") (class "Default")
      (node (ref "P2") (pin "34") (pinfunction "34_34") (pintype "passive"))
    )
    (net (code "236") (name "unconnected-(P2-Pad35)") (class "Default")
      (node (ref "P2") (pin "35") (pinfunction "35_35") (pintype "passive"))
    )
    (net (code "237") (name "unconnected-(P2-Pad36)") (class "Default")
      (node (ref "P2") (pin "36") (pinfunction "36_36") (pintype "passive"))
    )
    (net (code "238") (name "unconnected-(P2-Pad37)") (class "Default")
      (node (ref "P2") (pin "37") (pinfunction "37_37") (pintype "passive"))
    )
    (net (code "239") (name "unconnected-(P2-Pad38)") (class "Default")
      (node (ref "P2") (pin "38") (pinfunction "38_38") (pintype "passive"))
    )
    (net (code "240") (name "unconnected-(P2-Pad39)") (class "Default")
      (node (ref "P2") (pin "39") (pinfunction "39_39") (pintype "passive"))
    )
    (net (code "241") (name "unconnected-(P2-Pad40)") (class "Default")
      (node (ref "P2") (pin "40") (pinfunction "40_40") (pintype "passive"))
    )
    (net (code "242") (name "unconnected-(P2-Pad43)") (class "Default")
      (node (ref "P2") (pin "43") (pinfunction "43_43") (pintype "passive"))
    )
    (net (code "243") (name "unconnected-(P2-Pad44)") (class "Default")
      (node (ref "P2") (pin "44") (pinfunction "44_44") (pintype "passive"))
    )
    (net (code "244") (name "unconnected-(P2-Pad45)") (class "Default")
      (node (ref "P2") (pin "45") (pinfunction "45_45") (pintype "passive"))
    )
    (net (code "245") (name "unconnected-(P2-Pad46)") (class "Default")
      (node (ref "P2") (pin "46") (pinfunction "46_46") (pintype "passive"))
    )
    (net (code "246") (name "unconnected-(P2-Pad47)") (class "Default")
      (node (ref "P2") (pin "47") (pinfunction "47_47") (pintype "passive"))
    )
    (net (code "247") (name "unconnected-(P2-Pad48)") (class "Default")
      (node (ref "P2") (pin "48") (pinfunction "48_48") (pintype "passive"))
    )
    (net (code "248") (name "unconnected-(P2-Pad49)") (class "Default")
      (node (ref "P2") (pin "49") (pinfunction "49_49") (pintype "passive"))
    )
    (net (code "249") (name "unconnected-(P2-Pad50)") (class "Default")
      (node (ref "P2") (pin "50") (pinfunction "50_50") (pintype "passive"))
    )
    (net (code "250") (name "unconnected-(P2-Pad53)") (class "Default")
      (node (ref "P2") (pin "53") (pinfunction "53_53") (pintype "passive"))
    )
    (net (code "251") (name "unconnected-(P2-Pad54)") (class "Default")
      (node (ref "P2") (pin "54") (pinfunction "54_54") (pintype "passive"))
    )
    (net (code "252") (name "unconnected-(P2-Pad55)") (class "Default")
      (node (ref "P2") (pin "55") (pinfunction "55_55") (pintype "passive"))
    )
    (net (code "253") (name "unconnected-(P2-Pad56)") (class "Default")
      (node (ref "P2") (pin "56") (pinfunction "56_56") (pintype "passive"))
    )
    (net (code "254") (name "unconnected-(P2-Pad57)") (class "Default")
      (node (ref "P2") (pin "57") (pinfunction "57_57") (pintype "passive"))
    )
    (net (code "255") (name "unconnected-(P2-Pad58)") (class "Default")
      (node (ref "P2") (pin "58") (pinfunction "58_58") (pintype "passive"))
    )
    (net (code "256") (name "unconnected-(P2-Pad59)") (class "Default")
      (node (ref "P2") (pin "59") (pinfunction "59_59") (pintype "passive"))
    )
    (net (code "257") (name "unconnected-(P2-Pad60)") (class "Default")
      (node (ref "P2") (pin "60") (pinfunction "60_60") (pintype "passive"))
    )
    (net (code "258") (name "unconnected-(P2-PadHOLE)") (class "Default")
      (node (ref "P2") (pin "HOLE") (pinfunction "HOLE_HOLE") (pintype "passive"))
    )
    (net (code "259") (name "unconnected-(P3-Pad1)") (class "Default")
      (node (ref "P3") (pin "1") (pinfunction "1_1") (pintype "passive"))
    )
    (net (code "260") (name "unconnected-(P3-Pad2)") (class "Default")
      (node (ref "P3") (pin "2") (pinfunction "2_2") (pintype "passive"))
    )
    (net (code "261") (name "unconnected-(P3-Pad3)") (class "Default")
      (node (ref "P3") (pin "3") (pinfunction "3_3") (pintype "passive"))
    )
    (net (code "262") (name "unconnected-(P3-Pad4)") (class "Default")
      (node (ref "P3") (pin "4") (pinfunction "4_4") (pintype "passive"))
    )
    (net (code "263") (name "unconnected-(P3-Pad5)") (class "Default")
      (node (ref "P3") (pin "5") (pinfunction "5_5") (pintype "passive"))
    )
    (net (code "264") (name "unconnected-(P3-Pad6)") (class "Default")
      (node (ref "P3") (pin "6") (pinfunction "6_6") (pintype "passive"))
    )
    (net (code "265") (name "unconnected-(P3-Pad7)") (class "Default")
      (node (ref "P3") (pin "7") (pinfunction "7_7") (pintype "passive"))
    )
    (net (code "266") (name "unconnected-(P3-Pad8)") (class "Default")
      (node (ref "P3") (pin "8") (pinfunction "8_8") (pintype "passive"))
    )
    (net (code "267") (name "unconnected-(P3-Pad9)") (class "Default")
      (node (ref "P3") (pin "9") (pinfunction "9_9") (pintype "passive"))
    )
    (net (code "268") (name "unconnected-(P3-Pad10)") (class "Default")
      (node (ref "P3") (pin "10") (pinfunction "10_10") (pintype "passive"))
    )
    (net (code "269") (name "unconnected-(P3-Pad13)") (class "Default")
      (node (ref "P3") (pin "13") (pinfunction "13_13") (pintype "passive"))
    )
    (net (code "270") (name "unconnected-(P3-Pad14)") (class "Default")
      (node (ref "P3") (pin "14") (pinfunction "14_14") (pintype "passive"))
    )
    (net (code "271") (name "unconnected-(P3-Pad15)") (class "Default")
      (node (ref "P3") (pin "15") (pinfunction "15_15") (pintype "passive"))
    )
    (net (code "272") (name "unconnected-(P3-Pad16)") (class "Default")
      (node (ref "P3") (pin "16") (pinfunction "16_16") (pintype "passive"))
    )
    (net (code "273") (name "unconnected-(P3-Pad17)") (class "Default")
      (node (ref "P3") (pin "17") (pinfunction "17_17") (pintype "passive"))
    )
    (net (code "274") (name "unconnected-(P3-Pad18)") (class "Default")
      (node (ref "P3") (pin "18") (pinfunction "18_18") (pintype "passive"))
    )
    (net (code "275") (name "unconnected-(P3-Pad19)") (class "Default")
      (node (ref "P3") (pin "19") (pinfunction "19_19") (pintype "passive"))
    )
    (net (code "276") (name "unconnected-(P3-Pad20)") (class "Default")
      (node (ref "P3") (pin "20") (pinfunction "20_20") (pintype "passive"))
    )
    (net (code "277") (name "unconnected-(P3-Pad23)") (class "Default")
      (node (ref "P3") (pin "23") (pinfunction "23_23") (pintype "passive"))
    )
    (net (code "278") (name "unconnected-(P3-Pad24)") (class "Default")
      (node (ref "P3") (pin "24") (pinfunction "24_24") (pintype "passive"))
    )
    (net (code "279") (name "unconnected-(P3-Pad25)") (class "Default")
      (node (ref "P3") (pin "25") (pinfunction "25_25") (pintype "passive"))
    )
    (net (code "280") (name "unconnected-(P3-Pad26)") (class "Default")
      (node (ref "P3") (pin "26") (pinfunction "26_26") (pintype "passive"))
    )
    (net (code "281") (name "unconnected-(P3-Pad27)") (class "Default")
      (node (ref "P3") (pin "27") (pinfunction "27_27") (pintype "passive"))
    )
    (net (code "282") (name "unconnected-(P3-Pad28)") (class "Default")
      (node (ref "P3") (pin "28") (pinfunction "28_28") (pintype "passive"))
    )
    (net (code "283") (name "unconnected-(P3-Pad29)") (class "Default")
      (node (ref "P3") (pin "29") (pinfunction "29_29") (pintype "passive"))
    )
    (net (code "284") (name "unconnected-(P3-Pad30)") (class "Default")
      (node (ref "P3") (pin "30") (pinfunction "30_30") (pintype "passive"))
    )
    (net (code "285") (name "unconnected-(P3-Pad33)") (class "Default")
      (node (ref "P3") (pin "33") (pinfunction "33_33") (pintype "passive"))
    )
    (net (code "286") (name "unconnected-(P3-Pad34)") (class "Default")
      (node (ref "P3") (pin "34") (pinfunction "34_34") (pintype "passive"))
    )
    (net (code "287") (name "unconnected-(P3-Pad37)") (class "Default")
      (node (ref "P3") (pin "37") (pinfunction "37_37") (pintype "passive"))
    )
    (net (code "288") (name "unconnected-(P3-Pad38)") (class "Default")
      (node (ref "P3") (pin "38") (pinfunction "38_38") (pintype "passive"))
    )
    (net (code "289") (name "unconnected-(P3-Pad39)") (class "Default")
      (node (ref "P3") (pin "39") (pinfunction "39_39") (pintype "passive"))
    )
    (net (code "290") (name "unconnected-(P3-Pad40)") (class "Default")
      (node (ref "P3") (pin "40") (pinfunction "40_40") (pintype "passive"))
    )
    (net (code "291") (name "unconnected-(P3-Pad43)") (class "Default")
      (node (ref "P3") (pin "43") (pinfunction "43_43") (pintype "passive"))
    )
    (net (code "292") (name "unconnected-(P3-Pad44)") (class "Default")
      (node (ref "P3") (pin "44") (pinfunction "44_44") (pintype "passive"))
    )
    (net (code "293") (name "unconnected-(P3-Pad45)") (class "Default")
      (node (ref "P3") (pin "45") (pinfunction "45_45") (pintype "passive"))
    )
    (net (code "294") (name "unconnected-(P3-Pad46)") (class "Default")
      (node (ref "P3") (pin "46") (pinfunction "46_46") (pintype "passive"))
    )
    (net (code "295") (name "unconnected-(P3-Pad47)") (class "Default")
      (node (ref "P3") (pin "47") (pinfunction "47_47") (pintype "passive"))
    )
    (net (code "296") (name "unconnected-(P3-Pad48)") (class "Default")
      (node (ref "P3") (pin "48") (pinfunction "48_48") (pintype "passive"))
    )
    (net (code "297") (name "unconnected-(P3-Pad49)") (class "Default")
      (node (ref "P3") (pin "49") (pinfunction "49_49") (pintype "passive"))
    )
    (net (code "298") (name "unconnected-(P3-Pad50)") (class "Default")
      (node (ref "P3") (pin "50") (pinfunction "50_50") (pintype "passive"))
    )
    (net (code "299") (name "unconnected-(P3-Pad53)") (class "Default")
      (node (ref "P3") (pin "53") (pinfunction "53_53") (pintype "passive"))
    )
    (net (code "300") (name "unconnected-(P3-Pad54)") (class "Default")
      (node (ref "P3") (pin "54") (pinfunction "54_54") (pintype "passive"))
    )
    (net (code "301") (name "unconnected-(P3-Pad55)") (class "Default")
      (node (ref "P3") (pin "55") (pinfunction "55_55") (pintype "passive"))
    )
    (net (code "302") (name "unconnected-(P3-Pad56)") (class "Default")
      (node (ref "P3") (pin "56") (pinfunction "56_56") (pintype "passive"))
    )
    (net (code "303") (name "unconnected-(P3-Pad57)") (class "Default")
      (node (ref "P3") (pin "57") (pinfunction "57_57") (pintype "passive"))
    )
    (net (code "304") (name "unconnected-(P3-Pad58)") (class "Default")
      (node (ref "P3") (pin "58") (pinfunction "58_58") (pintype "passive"))
    )
    (net (code "305") (name "unconnected-(P3-Pad59)") (class "Default")
      (node (ref "P3") (pin "59") (pinfunction "59_59") (pintype "passive"))
    )
    (net (code "306") (name "unconnected-(P3-Pad60)") (class "Default")
      (node (ref "P3") (pin "60") (pinfunction "60_60") (pintype "passive"))
    )
    (net (code "307") (name "unconnected-(P3-PadHOLE)") (class "Default")
      (node (ref "P3") (pin "HOLE") (pinfunction "HOLE_HOLE") (pintype "passive"))
    )
    (net (code "308") (name "unconnected-(P4-Pad1)") (class "Default")
      (node (ref "P4") (pin "1") (pinfunction "1_1") (pintype "passive"))
    )
    (net (code "309") (name "unconnected-(P4-Pad2)") (class "Default")
      (node (ref "P4") (pin "2") (pinfunction "2_2") (pintype "passive"))
    )
    (net (code "310") (name "unconnected-(P4-Pad3)") (class "Default")
      (node (ref "P4") (pin "3") (pinfunction "3_3") (pintype "passive"))
    )
    (net (code "311") (name "unconnected-(P4-Pad4)") (class "Default")
      (node (ref "P4") (pin "4") (pinfunction "4_4") (pintype "passive"))
    )
    (net (code "312") (name "unconnected-(P4-Pad5)") (class "Default")
      (node (ref "P4") (pin "5") (pinfunction "5_5") (pintype "passive"))
    )
    (net (code "313") (name "unconnected-(P4-Pad6)") (class "Default")
      (node (ref "P4") (pin "6") (pinfunction "6_6") (pintype "passive"))
    )
    (net (code "314") (name "unconnected-(P4-Pad7)") (class "Default")
      (node (ref "P4") (pin "7") (pinfunction "7_7") (pintype "passive"))
    )
    (net (code "315") (name "unconnected-(P4-Pad8)") (class "Default")
      (node (ref "P4") (pin "8") (pinfunction "8_8") (pintype "passive"))
    )
    (net (code "316") (name "unconnected-(P4-Pad9)") (class "Default")
      (node (ref "P4") (pin "9") (pinfunction "9_9") (pintype "passive"))
    )
    (net (code "317") (name "unconnected-(P4-Pad10)") (class "Default")
      (node (ref "P4") (pin "10") (pinfunction "10_10") (pintype "passive"))
    )
    (net (code "318") (name "unconnected-(P4-Pad13)") (class "Default")
      (node (ref "P4") (pin "13") (pinfunction "13_13") (pintype "passive"))
    )
    (net (code "319") (name "unconnected-(P4-Pad14)") (class "Default")
      (node (ref "P4") (pin "14") (pinfunction "14_14") (pintype "passive"))
    )
    (net (code "320") (name "unconnected-(P4-Pad15)") (class "Default")
      (node (ref "P4") (pin "15") (pinfunction "15_15") (pintype "passive"))
    )
    (net (code "321") (name "unconnected-(P4-Pad16)") (class "Default")
      (node (ref "P4") (pin "16") (pinfunction "16_16") (pintype "passive"))
    )
    (net (code "322") (name "unconnected-(P4-Pad17)") (class "Default")
      (node (ref "P4") (pin "17") (pinfunction "17_17") (pintype "passive"))
    )
    (net (code "323") (name "unconnected-(P4-Pad18)") (class "Default")
      (node (ref "P4") (pin "18") (pinfunction "18_18") (pintype "passive"))
    )
    (net (code "324") (name "unconnected-(P4-Pad19)") (class "Default")
      (node (ref "P4") (pin "19") (pinfunction "19_19") (pintype "passive"))
    )
    (net (code "325") (name "unconnected-(P4-Pad20)") (class "Default")
      (node (ref "P4") (pin "20") (pinfunction "20_20") (pintype "passive"))
    )
    (net (code "326") (name "unconnected-(P4-Pad23)") (class "Default")
      (node (ref "P4") (pin "23") (pinfunction "23_23") (pintype "passive"))
    )
    (net (code "327") (name "unconnected-(P4-Pad24)") (class "Default")
      (node (ref "P4") (pin "24") (pinfunction "24_24") (pintype "passive"))
    )
    (net (code "328") (name "unconnected-(P4-Pad25)") (class "Default")
      (node (ref "P4") (pin "25") (pinfunction "25_25") (pintype "passive"))
    )
    (net (code "329") (name "unconnected-(P4-Pad26)") (class "Default")
      (node (ref "P4") (pin "26") (pinfunction "26_26") (pintype "passive"))
    )
    (net (code "330") (name "unconnected-(P4-Pad27)") (class "Default")
      (node (ref "P4") (pin "27") (pinfunction "27_27") (pintype "passive"))
    )
    (net (code "331") (name "unconnected-(P4-Pad28)") (class "Default")
      (node (ref "P4") (pin "28") (pinfunction "28_28") (pintype "passive"))
    )
    (net (code "332") (name "unconnected-(P4-Pad29)") (class "Default")
      (node (ref "P4") (pin "29") (pinfunction "29_29") (pintype "passive"))
    )
    (net (code "333") (name "unconnected-(P4-Pad30)") (class "Default")
      (node (ref "P4") (pin "30") (pinfunction "30_30") (pintype "passive"))
    )
    (net (code "334") (name "unconnected-(P4-Pad33)") (class "Default")
      (node (ref "P4") (pin "33") (pinfunction "33_33") (pintype "passive"))
    )
    (net (code "335") (name "unconnected-(P4-Pad34)") (class "Default")
      (node (ref "P4") (pin "34") (pinfunction "34_34") (pintype "passive"))
    )
    (net (code "336") (name "unconnected-(P4-Pad35)") (class "Default")
      (node (ref "P4") (pin "35") (pinfunction "35_35") (pintype "passive"))
    )
    (net (code "337") (name "unconnected-(P4-Pad36)") (class "Default")
      (node (ref "P4") (pin "36") (pinfunction "36_36") (pintype "passive"))
    )
    (net (code "338") (name "unconnected-(P4-Pad37)") (class "Default")
      (node (ref "P4") (pin "37") (pinfunction "37_37") (pintype "passive"))
    )
    (net (code "339") (name "unconnected-(P4-Pad38)") (class "Default")
      (node (ref "P4") (pin "38") (pinfunction "38_38") (pintype "passive"))
    )
    (net (code "340") (name "unconnected-(P4-Pad39)") (class "Default")
      (node (ref "P4") (pin "39") (pinfunction "39_39") (pintype "passive"))
    )
    (net (code "341") (name "unconnected-(P4-Pad40)") (class "Default")
      (node (ref "P4") (pin "40") (pinfunction "40_40") (pintype "passive"))
    )
    (net (code "342") (name "unconnected-(P4-Pad43)") (class "Default")
      (node (ref "P4") (pin "43") (pinfunction "43_43") (pintype "passive"))
    )
    (net (code "343") (name "unconnected-(P4-Pad44)") (class "Default")
      (node (ref "P4") (pin "44") (pinfunction "44_44") (pintype "passive"))
    )
    (net (code "344") (name "unconnected-(P4-Pad45)") (class "Default")
      (node (ref "P4") (pin "45") (pinfunction "45_45") (pintype "passive"))
    )
    (net (code "345") (name "unconnected-(P4-Pad46)") (class "Default")
      (node (ref "P4") (pin "46") (pinfunction "46_46") (pintype "passive"))
    )
    (net (code "346") (name "unconnected-(P4-Pad47)") (class "Default")
      (node (ref "P4") (pin "47") (pinfunction "47_47") (pintype "passive"))
    )
    (net (code "347") (name "unconnected-(P4-Pad48)") (class "Default")
      (node (ref "P4") (pin "48") (pinfunction "48_48") (pintype "passive"))
    )
    (net (code "348") (name "unconnected-(P4-Pad49)") (class "Default")
      (node (ref "P4") (pin "49") (pinfunction "49_49") (pintype "passive"))
    )
    (net (code "349") (name "unconnected-(P4-Pad50)") (class "Default")
      (node (ref "P4") (pin "50") (pinfunction "50_50") (pintype "passive"))
    )
    (net (code "350") (name "unconnected-(P4-Pad53)") (class "Default")
      (node (ref "P4") (pin "53") (pinfunction "53_53") (pintype "passive"))
    )
    (net (code "351") (name "unconnected-(P4-Pad54)") (class "Default")
      (node (ref "P4") (pin "54") (pinfunction "54_54") (pintype "passive"))
    )
    (net (code "352") (name "unconnected-(P4-Pad55)") (class "Default")
      (node (ref "P4") (pin "55") (pinfunction "55_55") (pintype "passive"))
    )
    (net (code "353") (name "unconnected-(P4-Pad56)") (class "Default")
      (node (ref "P4") (pin "56") (pinfunction "56_56") (pintype "passive"))
    )
    (net (code "354") (name "unconnected-(P4-Pad57)") (class "Default")
      (node (ref "P4") (pin "57") (pinfunction "57_57") (pintype "passive"))
    )
    (net (code "355") (name "unconnected-(P4-Pad58)") (class "Default")
      (node (ref "P4") (pin "58") (pinfunction "58_58") (pintype "passive"))
    )
    (net (code "356") (name "unconnected-(P4-Pad59)") (class "Default")
      (node (ref "P4") (pin "59") (pinfunction "59_59") (pintype "passive"))
    )
    (net (code "357") (name "unconnected-(P4-Pad60)") (class "Default")
      (node (ref "P4") (pin "60") (pinfunction "60_60") (pintype "passive"))
    )
    (net (code "358") (name "unconnected-(P4-PadHOLE)") (class "Default")
      (node (ref "P4") (pin "HOLE") (pinfunction "HOLE_HOLE") (pintype "passive"))
    )
    (net (code "359") (name "unconnected-(P17-Pad1)") (class "Default")
      (node (ref "P17") (pin "1") (pinfunction "1_1") (pintype "bidirectional+no_connect"))
    )
    (net (code "360") (name "unconnected-(P17-Pad12)") (class "Default")
      (node (ref "P17") (pin "12") (pinfunction "12_12") (pintype "bidirectional+no_connect"))
    )
    (net (code "361") (name "unconnected-(P17-Pad14)") (class "Default")
      (node (ref "P17") (pin "14") (pinfunction "14_14") (pintype "bidirectional+no_connect"))
    )
    (net (code "362") (name "unconnected-(P17-PadHOLE)") (class "Default")
      (node (ref "P17") (pin "HOLE") (pinfunction "HOLE_HOLE") (pintype "passive"))
    )
    (net (code "363") (name "unconnected-(P17-PadHOLE)_1") (class "Default")
      (node (ref "P17") (pin "HOLE") (pinfunction "HOLE_HOLE") (pintype "passive"))
    )
  )
)
